# BRD_EPM240.net
KiCad netlist of a schematic drawn in Altium Designer
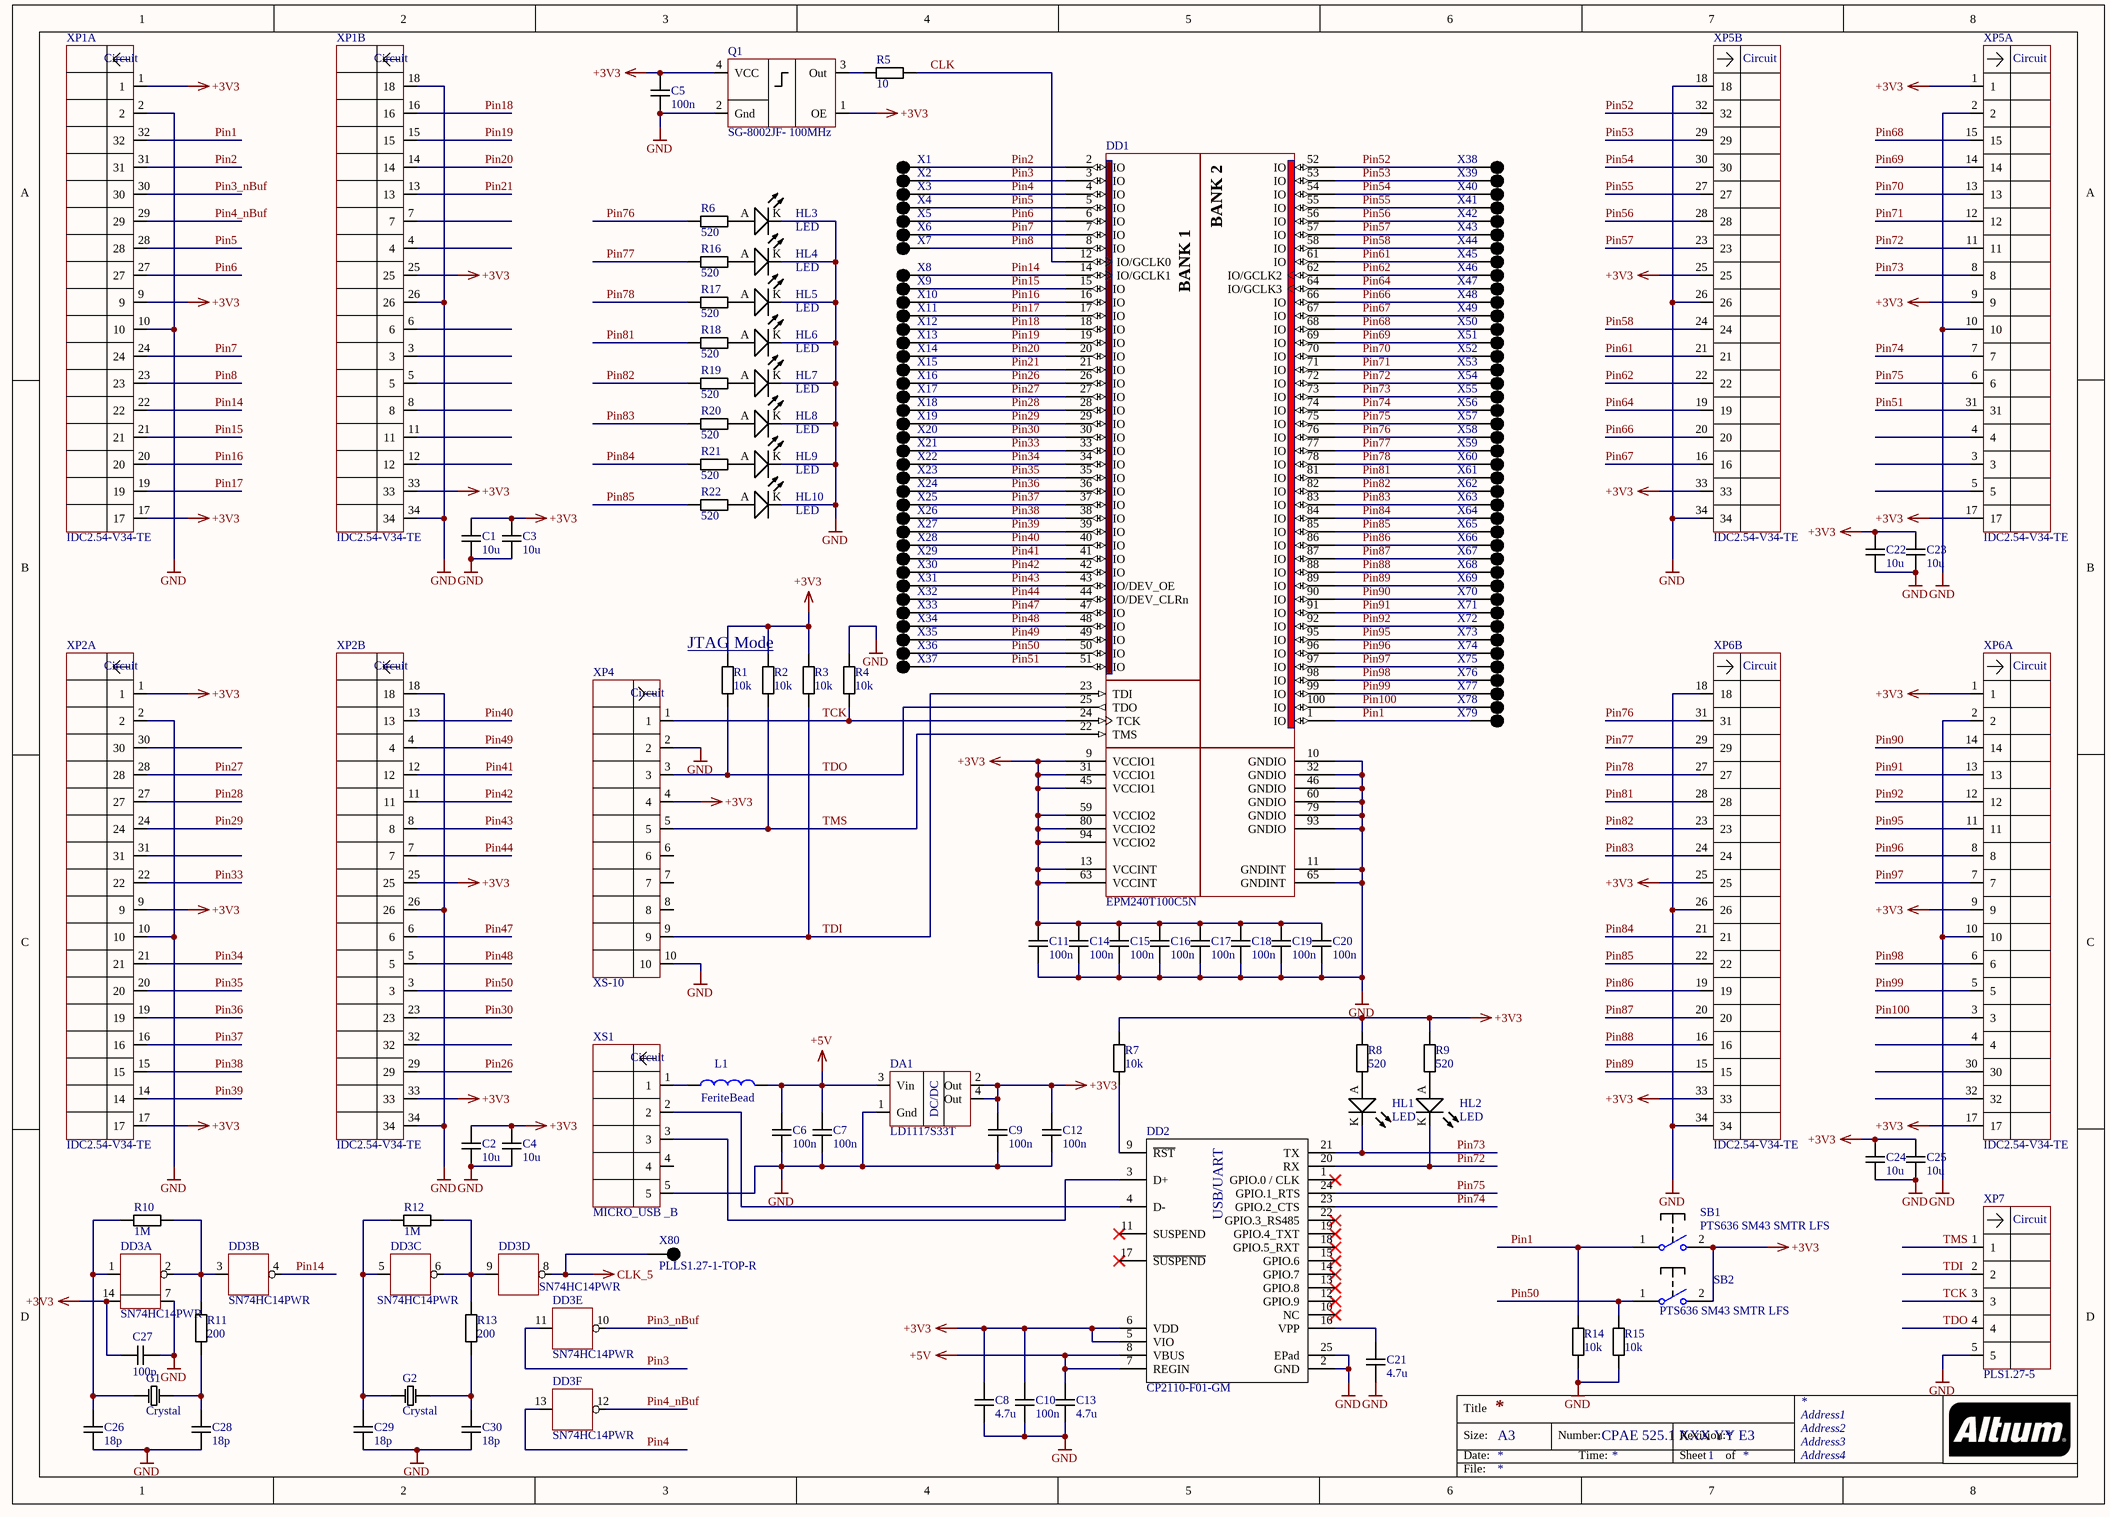
[diagram p0: BRD_EPM240.SchDoc]

(export (version "E")
  (design (tool "Eeschema 10.0.6"))
  (components
    (comp (ref "C1")
      (value "10u")
      (footprint "CAPC1608(0603)N")
      (description "?")
      (fields (field (name "PART NUMBER") "CAPC1608(0603)"))
      (libsource (lib "SssAccesDatbase") (part "Cap"))
    )
    (comp (ref "C2")
      (value "10u")
      (footprint "CAPC1608(0603)N")
      (description "?")
      (fields (field (name "PART NUMBER") "CAPC1608(0603)"))
      (libsource (lib "SssAccesDatbase") (part "Cap"))
    )
    (comp (ref "C3")
      (value "10u")
      (footprint "CAPC1608(0603)N")
      (description "?")
      (fields (field (name "PART NUMBER") "CAPC1608(0603)"))
      (libsource (lib "SssAccesDatbase") (part "Cap"))
    )
    (comp (ref "C4")
      (value "10u")
      (footprint "CAPC1608(0603)N")
      (description "?")
      (fields (field (name "PART NUMBER") "CAPC1608(0603)"))
      (libsource (lib "SssAccesDatbase") (part "Cap"))
    )
    (comp (ref "C5")
      (value "100n")
      (footprint "CAPC1608(0603)N")
      (description "?")
      (fields (field (name "PART NUMBER") "CAPC1608(0603)"))
      (libsource (lib "SssAccesDatbase") (part "Cap"))
    )
    (comp (ref "C6")
      (value "100n")
      (footprint "CAPC1608(0603)N")
      (description "?")
      (fields (field (name "PART NUMBER") "CAPC1608(0603)"))
      (libsource (lib "SssAccesDatbase") (part "Cap"))
    )
    (comp (ref "C7")
      (value "100n")
      (footprint "CAPC1608(0603)N")
      (description "?")
      (fields (field (name "PART NUMBER") "CAPC1608(0603)"))
      (libsource (lib "SssAccesDatbase") (part "Cap"))
    )
    (comp (ref "C8")
      (value "4.7u")
      (footprint "CAPC1608(0603)N")
      (description "?")
      (fields (field (name "PART NUMBER") "CAPC1608(0603)"))
      (libsource (lib "SssAccesDatbase") (part "Cap"))
    )
    (comp (ref "C9")
      (value "100n")
      (footprint "CAPC1608(0603)N")
      (description "?")
      (fields (field (name "PART NUMBER") "CAPC1608(0603)"))
      (libsource (lib "SssAccesDatbase") (part "Cap"))
    )
    (comp (ref "C10")
      (value "100n")
      (footprint "CAPC1608(0603)N")
      (description "?")
      (fields (field (name "PART NUMBER") "CAPC1608(0603)"))
      (libsource (lib "SssAccesDatbase") (part "Cap"))
    )
    (comp (ref "C11")
      (value "100n")
      (footprint "CAPC1608(0603)N")
      (description "?")
      (fields (field (name "PART NUMBER") "CAPC1608(0603)"))
      (libsource (lib "SssAccesDatbase") (part "Cap"))
    )
    (comp (ref "C12")
      (value "100n")
      (footprint "CAPC1608(0603)N")
      (description "?")
      (fields (field (name "PART NUMBER") "CAPC1608(0603)"))
      (libsource (lib "SssAccesDatbase") (part "Cap"))
    )
    (comp (ref "C13")
      (value "4.7u")
      (footprint "CAPC1608(0603)N")
      (description "?")
      (fields (field (name "PART NUMBER") "CAPC1608(0603)"))
      (libsource (lib "SssAccesDatbase") (part "Cap"))
    )
    (comp (ref "C14")
      (value "100n")
      (footprint "CAPC1608(0603)N")
      (description "?")
      (fields (field (name "PART NUMBER") "CAPC1608(0603)"))
      (libsource (lib "SssAccesDatbase") (part "Cap"))
    )
    (comp (ref "C15")
      (value "100n")
      (footprint "CAPC1608(0603)N")
      (description "?")
      (fields (field (name "PART NUMBER") "CAPC1608(0603)"))
      (libsource (lib "SssAccesDatbase") (part "Cap"))
    )
    (comp (ref "C16")
      (value "100n")
      (footprint "CAPC1608(0603)N")
      (description "?")
      (fields (field (name "PART NUMBER") "CAPC1608(0603)"))
      (libsource (lib "SssAccesDatbase") (part "Cap"))
    )
    (comp (ref "C17")
      (value "100n")
      (footprint "CAPC1608(0603)N")
      (description "?")
      (fields (field (name "PART NUMBER") "CAPC1608(0603)"))
      (libsource (lib "SssAccesDatbase") (part "Cap"))
    )
    (comp (ref "C18")
      (value "100n")
      (footprint "CAPC1608(0603)N")
      (description "?")
      (fields (field (name "PART NUMBER") "CAPC1608(0603)"))
      (libsource (lib "SssAccesDatbase") (part "Cap"))
    )
    (comp (ref "C19")
      (value "100n")
      (footprint "CAPC1608(0603)N")
      (description "?")
      (fields (field (name "PART NUMBER") "CAPC1608(0603)"))
      (libsource (lib "SssAccesDatbase") (part "Cap"))
    )
    (comp (ref "C20")
      (value "100n")
      (footprint "CAPC1608(0603)N")
      (description "?")
      (fields (field (name "PART NUMBER") "CAPC1608(0603)"))
      (libsource (lib "SssAccesDatbase") (part "Cap"))
    )
    (comp (ref "C21")
      (value "4.7u")
      (footprint "CAPC1608(0603)N")
      (description "?")
      (fields (field (name "PART NUMBER") "CAPC1608(0603)"))
      (libsource (lib "SssAccesDatbase") (part "Cap"))
    )
    (comp (ref "C22")
      (value "10u")
      (footprint "CAPC1608(0603)N")
      (description "?")
      (fields (field (name "PART NUMBER") "CAPC1608(0603)"))
      (libsource (lib "SssAccesDatbase") (part "Cap"))
    )
    (comp (ref "C23")
      (value "10u")
      (footprint "CAPC1608(0603)N")
      (description "?")
      (fields (field (name "PART NUMBER") "CAPC1608(0603)"))
      (libsource (lib "SssAccesDatbase") (part "Cap"))
    )
    (comp (ref "C24")
      (value "10u")
      (footprint "CAPC1608(0603)N")
      (description "?")
      (fields (field (name "PART NUMBER") "CAPC1608(0603)"))
      (libsource (lib "SssAccesDatbase") (part "Cap"))
    )
    (comp (ref "C25")
      (value "10u")
      (footprint "CAPC1608(0603)N")
      (description "?")
      (fields (field (name "PART NUMBER") "CAPC1608(0603)"))
      (libsource (lib "SssAccesDatbase") (part "Cap"))
    )
    (comp (ref "C26")
      (value "18p")
      (footprint "CAPC1608(0603)N")
      (description "?")
      (fields (field (name "PART NUMBER") "CAPC1608(0603)"))
      (libsource (lib "SssAccesDatbase") (part "Cap"))
    )
    (comp (ref "C27")
      (value "100p")
      (footprint "CAPC1608(0603)N")
      (description "?")
      (fields (field (name "PART NUMBER") "CAPC1608(0603)"))
      (libsource (lib "SssAccesDatbaseDYandex") (part "Cap"))
    )
    (comp (ref "C28")
      (value "18p")
      (footprint "CAPC1608(0603)N")
      (description "?")
      (fields (field (name "PART NUMBER") "CAPC1608(0603)"))
      (libsource (lib "SssAccesDatbase") (part "Cap"))
    )
    (comp (ref "C29")
      (value "18p")
      (footprint "CAPC1608(0603)N")
      (description "?")
      (fields (field (name "PART NUMBER") "CAPC1608(0603)"))
      (libsource (lib "SssAccesDatbase") (part "Cap"))
    )
    (comp (ref "C30")
      (value "18p")
      (footprint "CAPC1608(0603)N")
      (description "?")
      (fields (field (name "PART NUMBER") "CAPC1608(0603)"))
      (libsource (lib "SssAccesDatbase") (part "Cap"))
    )
    (comp (ref "DA1")
      (value "LD1117S33T")
      (footprint "SOT223_M")
      (libsource (lib "ADdatabaseLibfile") (part "LD1117S33T"))
    )
    (comp (ref "DD1")
      (value "EPM240T100C5N")
      (footprint "TQFP100_M")
      (fields (field (name "PUBLISHER") "Altium Limited"))
      (libsource (lib "SssAccesDatbase") (part "EPM240T100C5N"))
    )
    (comp (ref "DD2")
      (value "CP2110-F01-GM")
      (footprint "QFN24_N")
      (description "USB Bridge, USB to UART USB 2.0 UART Interface 24-QFN (4x4)")
      (fields (field (name "DIGI-KEY PART NUMBER") "336-2006-5-ND"))
      (libsource (lib "SssAccesDatbase") (part "CP2110-F01-GM"))
    )
    (comp (ref "DD3")
      (value "SN74HC14PWR")
      (footprint "TSSOP14")
      (description "IC INVERTER SCHMITT 6CH 14TSSOP")
      (libsource (lib "SssAccesDatbase") (part "74HC14"))
    )
    (comp (ref "G1")
      (value "Crystal")
      (footprint "HC-49/S")
      (description "Crystal HC-49/S")
      (libsource (lib "SssAccesDatbaseDYandex") (part "Crystal"))
    )
    (comp (ref "G2")
      (value "Crystal")
      (footprint "HC-49/S")
      (description "Crystal HC-49/S")
      (libsource (lib "SssAccesDatbaseDYandex") (part "Crystal"))
    )
    (comp (ref "HL1")
      (value "LED")
      (footprint "LED-0603-BLUE")
      (description "LED BLUE DIFFUSED 0603 SMD")
      (fields
        (field (name "PART NUMBER") "LED-0603-BLUE")
        (field (name "DIGI-KEY PART NUMBER") "732-12013-1-ND")
      )
      (libsource (lib "SssAccesDatbase") (part "LED"))
    )
    (comp (ref "HL2")
      (value "LED")
      (footprint "LED-0603-GREEN")
      (description "LED GREEN DIFFUSED 0603 SMD")
      (fields
        (field (name "PART NUMBER") "LED-0603-GREEN")
        (field (name "DIGI-KEY PART NUMBER") "732-12017-1-ND")
      )
      (libsource (lib "SssAccesDatbase") (part "LED"))
    )
    (comp (ref "HL3")
      (value "LED")
      (footprint "LED-0603-GREEN")
      (description "LED GREEN DIFFUSED 0603 SMD")
      (fields
        (field (name "PART NUMBER") "LED-0603-GREEN")
        (field (name "DIGI-KEY PART NUMBER") "732-12017-1-ND")
      )
      (libsource (lib "SssAccesDatbase") (part "LED"))
    )
    (comp (ref "HL4")
      (value "LED")
      (footprint "LED-0603-GREEN")
      (description "LED BLUE DIFFUSED 0603 SMD")
      (fields
        (field (name "PART NUMBER") "LED-0603-BLUE")
        (field (name "DIGI-KEY PART NUMBER") "732-12013-1-ND")
      )
      (libsource (lib "SssAccesDatbase") (part "LED"))
    )
    (comp (ref "HL5")
      (value "LED")
      (footprint "LED-0603-GREEN")
      (description "LED BLUE DIFFUSED 0603 SMD")
      (fields
        (field (name "PART NUMBER") "LED-0603-BLUE")
        (field (name "DIGI-KEY PART NUMBER") "732-12013-1-ND")
      )
      (libsource (lib "SssAccesDatbase") (part "LED"))
    )
    (comp (ref "HL6")
      (value "LED")
      (footprint "LED-0603-GREEN")
      (description "LED BLUE DIFFUSED 0603 SMD")
      (fields
        (field (name "PART NUMBER") "LED-0603-BLUE")
        (field (name "DIGI-KEY PART NUMBER") "732-12013-1-ND")
      )
      (libsource (lib "SssAccesDatbase") (part "LED"))
    )
    (comp (ref "HL7")
      (value "LED")
      (footprint "LED-0603-GREEN")
      (description "LED BLUE DIFFUSED 0603 SMD")
      (fields
        (field (name "PART NUMBER") "LED-0603-BLUE")
        (field (name "DIGI-KEY PART NUMBER") "732-12013-1-ND")
      )
      (libsource (lib "SssAccesDatbase") (part "LED"))
    )
    (comp (ref "HL8")
      (value "LED")
      (footprint "LED-0603-GREEN")
      (description "LED BLUE DIFFUSED 0603 SMD")
      (fields
        (field (name "PART NUMBER") "LED-0603-BLUE")
        (field (name "DIGI-KEY PART NUMBER") "732-12013-1-ND")
      )
      (libsource (lib "SssAccesDatbase") (part "LED"))
    )
    (comp (ref "HL9")
      (value "LED")
      (footprint "LED-0603-GREEN")
      (description "LED GREEN DIFFUSED 0603 SMD")
      (fields
        (field (name "PART NUMBER") "LED-0603-GREEN")
        (field (name "DIGI-KEY PART NUMBER") "732-12017-1-ND")
      )
      (libsource (lib "SssAccesDatbase") (part "LED"))
    )
    (comp (ref "HL10")
      (value "LED")
      (footprint "LED-0603-GREEN")
      (description "LED GREEN DIFFUSED 0603 SMD")
      (fields
        (field (name "PART NUMBER") "LED-0603-GREEN")
        (field (name "DIGI-KEY PART NUMBER") "732-12017-1-ND")
      )
      (libsource (lib "SssAccesDatbase") (part "LED"))
    )
    (comp (ref "L1")
      (value "FeriteBead")
      (footprint "INDC1608(0603)N")
      (fields (field (name "PART NUMBER") "INDC1608(0603)"))
      (libsource (lib "ADdatabaseLibfile") (part "L"))
    )
    (comp (ref "Q1")
      (value "SG-8002JF- 100MHz")
      (footprint "SG-8002JF")
      (fields (field (name "PART NUMBER") "SG-8002JF"))
      (libsource (lib "ADdatabaseLibfile") (part "SG-8002JF"))
    )
    (comp (ref "R1")
      (value "10k")
      (footprint "1608[0603]:RESC1608(0603)N")
      (fields (field (name "PART NUMBER") "RESC1005(0402)") (field (name "DIGI-KEY PART NUMBER") "???"))
      (libsource (lib "SssAccesDatbaseDYandex") (part "Resistor general"))
    )
    (comp (ref "R2")
      (value "10k")
      (footprint "1608[0603]:RESC1608(0603)N")
      (fields (field (name "PART NUMBER") "RESC1005(0402)") (field (name "DIGI-KEY PART NUMBER") "???"))
      (libsource (lib "SssAccesDatbaseDYandex") (part "Resistor general"))
    )
    (comp (ref "R3")
      (value "10k")
      (footprint "1608[0603]:RESC1608(0603)N")
      (fields (field (name "PART NUMBER") "RESC1005(0402)") (field (name "DIGI-KEY PART NUMBER") "???"))
      (libsource (lib "SssAccesDatbaseDYandex") (part "Resistor general"))
    )
    (comp (ref "R4")
      (value "10k")
      (footprint "1608[0603]:RESC1608(0603)N")
      (fields (field (name "PART NUMBER") "RESC1005(0402)") (field (name "DIGI-KEY PART NUMBER") "???"))
      (libsource (lib "SssAccesDatbaseDYandex") (part "Resistor general"))
    )
    (comp (ref "R5")
      (value "10")
      (footprint "RESC1608(0603)N")
      (fields (field (name "PART NUMBER") "RESC1608(0603)") (field (name "DIGI-KEY PART NUMBER") "???"))
      (libsource (lib "SssAccesDatbase") (part "Resistor general"))
    )
    (comp (ref "R6")
      (value "520")
      (footprint "RESC1608(0603)N")
      (fields (field (name "PART NUMBER") "RESC1608(0603)") (field (name "DIGI-KEY PART NUMBER") "???"))
      (libsource (lib "") (part "Resistor general_1"))
    )
    (comp (ref "R7")
      (value "10k")
      (footprint "1608[0603]:RESC1608(0603)N")
      (fields (field (name "PART NUMBER") "RESC1005(0402)") (field (name "DIGI-KEY PART NUMBER") "???"))
      (libsource (lib "") (part "Resistor general_2"))
    )
    (comp (ref "R8")
      (value "520")
      (footprint "1608[0603]:RESC1608(0603)N")
      (fields (field (name "PART NUMBER") "RESC1608(0603)") (field (name "DIGI-KEY PART NUMBER") "???"))
      (libsource (lib "SssAccesDatbaseDYandex") (part "Resistor general"))
    )
    (comp (ref "R9")
      (value "520")
      (footprint "1608[0603]:RESC1608(0603)N")
      (fields (field (name "PART NUMBER") "RESC1608(0603)") (field (name "DIGI-KEY PART NUMBER") "???"))
      (libsource (lib "SssAccesDatbaseDYandex") (part "Resistor general"))
    )
    (comp (ref "R10")
      (value "1M")
      (footprint "RESC1608(0603)N")
      (fields (field (name "PART NUMBER") "RESC1608(0603)") (field (name "DIGI-KEY PART NUMBER") "???"))
      (libsource (lib "SssAccesDatbaseDYandex") (part "Resistor general"))
    )
    (comp (ref "R11")
      (value "200")
      (footprint "RESC1608(0603)N")
      (fields (field (name "PART NUMBER") "RESC1608(0603)") (field (name "DIGI-KEY PART NUMBER") "???"))
      (libsource (lib "") (part "Resistor general_3"))
    )
    (comp (ref "R12")
      (value "1M")
      (footprint "RESC1608(0603)N")
      (fields (field (name "PART NUMBER") "RESC1608(0603)") (field (name "DIGI-KEY PART NUMBER") "???"))
      (libsource (lib "SssAccesDatbaseDYandex") (part "Resistor general"))
    )
    (comp (ref "R13")
      (value "200")
      (footprint "RESC1608(0603)N")
      (fields (field (name "PART NUMBER") "RESC1608(0603)") (field (name "DIGI-KEY PART NUMBER") "???"))
      (libsource (lib "") (part "Resistor general_3"))
    )
    (comp (ref "R14")
      (value "10k")
      (footprint "RESC1608(0603)N")
      (fields (field (name "PART NUMBER") "RESC1005(0402)") (field (name "DIGI-KEY PART NUMBER") "???"))
      (libsource (lib "") (part "Resistor general_2"))
    )
    (comp (ref "R15")
      (value "10k")
      (footprint "RESC1608(0603)N")
      (fields (field (name "PART NUMBER") "RESC1005(0402)") (field (name "DIGI-KEY PART NUMBER") "???"))
      (libsource (lib "") (part "Resistor general_2"))
    )
    (comp (ref "R16")
      (value "520")
      (footprint "RESC1608(0603)N")
      (fields (field (name "PART NUMBER") "RESC1608(0603)") (field (name "DIGI-KEY PART NUMBER") "???"))
      (libsource (lib "") (part "Resistor general_1"))
    )
    (comp (ref "R17")
      (value "520")
      (footprint "RESC1608(0603)N")
      (fields (field (name "PART NUMBER") "RESC1608(0603)") (field (name "DIGI-KEY PART NUMBER") "???"))
      (libsource (lib "") (part "Resistor general_1"))
    )
    (comp (ref "R18")
      (value "520")
      (footprint "RESC1608(0603)N")
      (fields (field (name "PART NUMBER") "RESC1608(0603)") (field (name "DIGI-KEY PART NUMBER") "???"))
      (libsource (lib "") (part "Resistor general_1"))
    )
    (comp (ref "R19")
      (value "520")
      (footprint "RESC1608(0603)N")
      (fields (field (name "PART NUMBER") "RESC1608(0603)") (field (name "DIGI-KEY PART NUMBER") "???"))
      (libsource (lib "") (part "Resistor general_1"))
    )
    (comp (ref "R20")
      (value "520")
      (footprint "RESC1608(0603)N")
      (fields (field (name "PART NUMBER") "RESC1608(0603)") (field (name "DIGI-KEY PART NUMBER") "???"))
      (libsource (lib "") (part "Resistor general_1"))
    )
    (comp (ref "R21")
      (value "520")
      (footprint "RESC1608(0603)N")
      (fields (field (name "PART NUMBER") "RESC1608(0603)") (field (name "DIGI-KEY PART NUMBER") "???"))
      (libsource (lib "") (part "Resistor general_1"))
    )
    (comp (ref "R22")
      (value "520")
      (footprint "RESC1608(0603)N")
      (fields (field (name "PART NUMBER") "RESC1608(0603)") (field (name "DIGI-KEY PART NUMBER") "???"))
      (libsource (lib "") (part "Resistor general_1"))
    )
    (comp (ref "SB1")
      (value "PTS636 SM43 SMTR LFS")
      (footprint "PTS636 SM43 SMTR LFS")
      (description "Tactile Switches Tact 50mA 12VDC, 6.0x3.5, 4.3mm H, 180gf, G leads, No ground pin, Black Actuator")
      (fields (field (name "MOUSER PART NUMBER") "611-PTS636SM43SMTRLF"))
      (libsource (lib "SssAccesDatbase") (part "SW-SPST"))
    )
    (comp (ref "SB2")
      (value "PTS636 SM43 SMTR LFS")
      (footprint "PTS636 SM43 SMTR LFS")
      (description "Tactile Switches Tact 50mA 12VDC, 6.0x3.5, 4.3mm H, 180gf, G leads, No ground pin, Black Actuator")
      (fields (field (name "MOUSER PART NUMBER") "611-PTS636SM43SMTRLF"))
      (libsource (lib "SssAccesDatbase") (part "SW-SPST"))
    )
    (comp (ref "X1")
      (value "X1-PLLD1.27-1")
      (footprint "PLLS1.27-1")
      (libsource (lib "SssAccesDatbase") (part "X1_1"))
    )
    (comp (ref "X2")
      (value "X1-PLLD1.27-1")
      (footprint "PLLS1.27-1")
      (libsource (lib "SssAccesDatbase") (part "X1_1"))
    )
    (comp (ref "X3")
      (value "X1-PLLD1.27-1")
      (footprint "PLLS1.27-1")
      (libsource (lib "SssAccesDatbase") (part "X1_1"))
    )
    (comp (ref "X4")
      (value "X1-PLLD1.27-1")
      (footprint "PLLS1.27-1")
      (libsource (lib "SssAccesDatbase") (part "X1_1"))
    )
    (comp (ref "X5")
      (value "X1-PLLD1.27-1")
      (footprint "PLLS1.27-1")
      (libsource (lib "SssAccesDatbase") (part "X1_1"))
    )
    (comp (ref "X6")
      (value "X1-PLLD1.27-1")
      (footprint "PLLS1.27-1")
      (libsource (lib "SssAccesDatbase") (part "X1_1"))
    )
    (comp (ref "X7")
      (value "X1-PLLD1.27-1")
      (footprint "PLLS1.27-1")
      (libsource (lib "SssAccesDatbase") (part "X1_1"))
    )
    (comp (ref "X8")
      (value "X1-PLLD1.27-1")
      (footprint "PLLS1.27-1")
      (libsource (lib "SssAccesDatbase") (part "X1_1"))
    )
    (comp (ref "X9")
      (value "X1-PLLD1.27-1")
      (footprint "PLLS1.27-1")
      (libsource (lib "SssAccesDatbase") (part "X1_1"))
    )
    (comp (ref "X10")
      (value "X1-PLLD1.27-1")
      (footprint "PLLS1.27-1")
      (libsource (lib "SssAccesDatbase") (part "X1_1"))
    )
    (comp (ref "X11")
      (value "X1-PLLD1.27-1")
      (footprint "PLLS1.27-1")
      (libsource (lib "SssAccesDatbase") (part "X1_1"))
    )
    (comp (ref "X12")
      (value "X1-PLLD1.27-1")
      (footprint "PLLS1.27-1")
      (libsource (lib "SssAccesDatbase") (part "X1_1"))
    )
    (comp (ref "X13")
      (value "X1-PLLD1.27-1")
      (footprint "PLLS1.27-1")
      (libsource (lib "SssAccesDatbase") (part "X1_1"))
    )
    (comp (ref "X14")
      (value "X1-PLLD1.27-1")
      (footprint "PLLS1.27-1")
      (libsource (lib "SssAccesDatbase") (part "X1_1"))
    )
    (comp (ref "X15")
      (value "X1-PLLD1.27-1")
      (footprint "PLLS1.27-1")
      (libsource (lib "SssAccesDatbase") (part "X1_1"))
    )
    (comp (ref "X16")
      (value "X1-PLLD1.27-1")
      (footprint "PLLS1.27-1")
      (libsource (lib "SssAccesDatbase") (part "X1_1"))
    )
    (comp (ref "X17")
      (value "X1-PLLD1.27-1")
      (footprint "PLLS1.27-1")
      (libsource (lib "SssAccesDatbase") (part "X1_1"))
    )
    (comp (ref "X18")
      (value "X1-PLLD1.27-1")
      (footprint "PLLS1.27-1")
      (libsource (lib "SssAccesDatbase") (part "X1_1"))
    )
    (comp (ref "X19")
      (value "X1-PLLD1.27-1")
      (footprint "PLLS1.27-1")
      (libsource (lib "SssAccesDatbase") (part "X1_1"))
    )
    (comp (ref "X20")
      (value "X1-PLLD1.27-1")
      (footprint "PLLS1.27-1")
      (libsource (lib "SssAccesDatbase") (part "X1_1"))
    )
    (comp (ref "X21")
      (value "X1-PLLD1.27-1")
      (footprint "PLLS1.27-1")
      (libsource (lib "SssAccesDatbase") (part "X1_1"))
    )
    (comp (ref "X22")
      (value "X1-PLLD1.27-1")
      (footprint "PLLS1.27-1")
      (libsource (lib "SssAccesDatbase") (part "X1_1"))
    )
    (comp (ref "X23")
      (value "X1-PLLD1.27-1")
      (footprint "PLLS1.27-1")
      (libsource (lib "SssAccesDatbase") (part "X1_1"))
    )
    (comp (ref "X24")
      (value "X1-PLLD1.27-1")
      (footprint "PLLS1.27-1")
      (libsource (lib "SssAccesDatbase") (part "X1_1"))
    )
    (comp (ref "X25")
      (value "X1-PLLD1.27-1")
      (footprint "PLLS1.27-1")
      (libsource (lib "SssAccesDatbase") (part "X1_1"))
    )
    (comp (ref "X26")
      (value "X1-PLLD1.27-1")
      (footprint "PLLS1.27-1")
      (libsource (lib "SssAccesDatbase") (part "X1_1"))
    )
    (comp (ref "X27")
      (value "X1-PLLD1.27-1")
      (footprint "PLLS1.27-1")
      (libsource (lib "SssAccesDatbase") (part "X1_1"))
    )
    (comp (ref "X28")
      (value "X1-PLLD1.27-1")
      (footprint "PLLS1.27-1")
      (libsource (lib "SssAccesDatbase") (part "X1_1"))
    )
    (comp (ref "X29")
      (value "X1-PLLD1.27-1")
      (footprint "PLLS1.27-1")
      (libsource (lib "SssAccesDatbase") (part "X1_1"))
    )
    (comp (ref "X30")
      (value "X1-PLLD1.27-1")
      (footprint "PLLS1.27-1")
      (libsource (lib "SssAccesDatbase") (part "X1_1"))
    )
    (comp (ref "X31")
      (value "X1-PLLD1.27-1")
      (footprint "PLLS1.27-1")
      (libsource (lib "SssAccesDatbase") (part "X1_1"))
    )
    (comp (ref "X32")
      (value "X1-PLLD1.27-1")
      (footprint "PLLS1.27-1")
      (libsource (lib "SssAccesDatbase") (part "X1_1"))
    )
    (comp (ref "X33")
      (value "X1-PLLD1.27-1")
      (footprint "PLLS1.27-1")
      (libsource (lib "SssAccesDatbase") (part "X1_1"))
    )
    (comp (ref "X34")
      (value "X1-PLLD1.27-1")
      (footprint "PLLS1.27-1")
      (libsource (lib "SssAccesDatbase") (part "X1_1"))
    )
    (comp (ref "X35")
      (value "X1-PLLD1.27-1")
      (footprint "PLLS1.27-1")
      (libsource (lib "SssAccesDatbase") (part "X1_1"))
    )
    (comp (ref "X36")
      (value "X1-PLLD1.27-1")
      (footprint "PLLS1.27-1")
      (libsource (lib "SssAccesDatbase") (part "X1_1"))
    )
    (comp (ref "X37")
      (value "X1-PLLD1.27-1")
      (footprint "PLLS1.27-1")
      (libsource (lib "SssAccesDatbase") (part "X1_1"))
    )
    (comp (ref "X38")
      (value "X1-PLLD1.27-1")
      (footprint "PLLS1.27-1")
      (libsource (lib "SssAccesDatbase") (part "X1_1"))
    )
    (comp (ref "X39")
      (value "X1-PLLD1.27-1")
      (footprint "PLLS1.27-1")
      (libsource (lib "SssAccesDatbase") (part "X1_1"))
    )
    (comp (ref "X40")
      (value "X1-PLLD1.27-1")
      (footprint "PLLS1.27-1")
      (libsource (lib "SssAccesDatbase") (part "X1_1"))
    )
    (comp (ref "X41")
      (value "X1-PLLD1.27-1")
      (footprint "PLLS1.27-1")
      (libsource (lib "SssAccesDatbase") (part "X1_1"))
    )
    (comp (ref "X42")
      (value "X1-PLLD1.27-1")
      (footprint "PLLS1.27-1")
      (libsource (lib "SssAccesDatbase") (part "X1_1"))
    )
    (comp (ref "X43")
      (value "X1-PLLD1.27-1")
      (footprint "PLLS1.27-1")
      (libsource (lib "SssAccesDatbase") (part "X1_1"))
    )
    (comp (ref "X44")
      (value "X1-PLLD1.27-1")
      (footprint "PLLS1.27-1")
      (libsource (lib "SssAccesDatbase") (part "X1_1"))
    )
    (comp (ref "X45")
      (value "X1-PLLD1.27-1")
      (footprint "PLLS1.27-1")
      (libsource (lib "SssAccesDatbase") (part "X1_1"))
    )
    (comp (ref "X46")
      (value "X1-PLLD1.27-1")
      (footprint "PLLS1.27-1")
      (libsource (lib "SssAccesDatbase") (part "X1_1"))
    )
    (comp (ref "X47")
      (value "X1-PLLD1.27-1")
      (footprint "PLLS1.27-1")
      (libsource (lib "SssAccesDatbase") (part "X1_1"))
    )
    (comp (ref "X48")
      (value "X1-PLLD1.27-1")
      (footprint "PLLS1.27-1")
      (libsource (lib "SssAccesDatbase") (part "X1_1"))
    )
    (comp (ref "X49")
      (value "X1-PLLD1.27-1")
      (footprint "PLLS1.27-1")
      (libsource (lib "SssAccesDatbase") (part "X1_1"))
    )
    (comp (ref "X50")
      (value "X1-PLLD1.27-1")
      (footprint "PLLS1.27-1")
      (libsource (lib "SssAccesDatbase") (part "X1_1"))
    )
    (comp (ref "X51")
      (value "X1-PLLD1.27-1")
      (footprint "PLLS1.27-1")
      (libsource (lib "SssAccesDatbase") (part "X1_1"))
    )
    (comp (ref "X52")
      (value "X1-PLLD1.27-1")
      (footprint "PLLS1.27-1")
      (libsource (lib "SssAccesDatbase") (part "X1_1"))
    )
    (comp (ref "X53")
      (value "X1-PLLD1.27-1")
      (footprint "PLLS1.27-1")
      (libsource (lib "SssAccesDatbase") (part "X1_1"))
    )
    (comp (ref "X54")
      (value "X1-PLLD1.27-1")
      (footprint "PLLS1.27-1")
      (libsource (lib "SssAccesDatbase") (part "X1_1"))
    )
    (comp (ref "X55")
      (value "X1-PLLD1.27-1")
      (footprint "PLLS1.27-1")
      (libsource (lib "SssAccesDatbase") (part "X1_1"))
    )
    (comp (ref "X56")
      (value "X1-PLLD1.27-1")
      (footprint "PLLS1.27-1")
      (libsource (lib "SssAccesDatbase") (part "X1_1"))
    )
    (comp (ref "X57")
      (value "X1-PLLD1.27-1")
      (footprint "PLLS1.27-1")
      (libsource (lib "SssAccesDatbase") (part "X1_1"))
    )
    (comp (ref "X58")
      (value "X1-PLLD1.27-1")
      (footprint "PLLS1.27-1")
      (libsource (lib "SssAccesDatbase") (part "X1_1"))
    )
    (comp (ref "X59")
      (value "X1-PLLD1.27-1")
      (footprint "PLLS1.27-1")
      (libsource (lib "SssAccesDatbase") (part "X1_1"))
    )
    (comp (ref "X60")
      (value "X1-PLLD1.27-1")
      (footprint "PLLS1.27-1")
      (libsource (lib "SssAccesDatbase") (part "X1_1"))
    )
    (comp (ref "X61")
      (value "X1-PLLD1.27-1")
      (footprint "PLLS1.27-1")
      (libsource (lib "SssAccesDatbase") (part "X1_1"))
    )
    (comp (ref "X62")
      (value "X1-PLLD1.27-1")
      (footprint "PLLS1.27-1")
      (libsource (lib "SssAccesDatbase") (part "X1_1"))
    )
    (comp (ref "X63")
      (value "X1-PLLD1.27-1")
      (footprint "PLLS1.27-1")
      (libsource (lib "SssAccesDatbase") (part "X1_1"))
    )
    (comp (ref "X64")
      (value "X1-PLLD1.27-1")
      (footprint "PLLS1.27-1")
      (libsource (lib "SssAccesDatbase") (part "X1_1"))
    )
    (comp (ref "X65")
      (value "X1-PLLD1.27-1")
      (footprint "PLLS1.27-1")
      (libsource (lib "SssAccesDatbase") (part "X1_1"))
    )
    (comp (ref "X66")
      (value "X1-PLLD1.27-1")
      (footprint "PLLS1.27-1")
      (libsource (lib "SssAccesDatbase") (part "X1_1"))
    )
    (comp (ref "X67")
      (value "X1-PLLD1.27-1")
      (footprint "PLLS1.27-1")
      (libsource (lib "SssAccesDatbase") (part "X1_1"))
    )
    (comp (ref "X68")
      (value "X1-PLLD1.27-1")
      (footprint "PLLS1.27-1")
      (libsource (lib "SssAccesDatbase") (part "X1_1"))
    )
    (comp (ref "X69")
      (value "X1-PLLD1.27-1")
      (footprint "PLLS1.27-1")
      (libsource (lib "SssAccesDatbase") (part "X1_1"))
    )
    (comp (ref "X70")
      (value "X1-PLLD1.27-1")
      (footprint "PLLS1.27-1")
      (libsource (lib "SssAccesDatbase") (part "X1_1"))
    )
    (comp (ref "X71")
      (value "X1-PLLD1.27-1")
      (footprint "PLLS1.27-1")
      (libsource (lib "SssAccesDatbase") (part "X1_1"))
    )
    (comp (ref "X72")
      (value "X1-PLLD1.27-1")
      (footprint "PLLS1.27-1")
      (libsource (lib "SssAccesDatbase") (part "X1_1"))
    )
    (comp (ref "X73")
      (value "X1-PLLD1.27-1")
      (footprint "PLLS1.27-1")
      (libsource (lib "SssAccesDatbase") (part "X1_1"))
    )
    (comp (ref "X74")
      (value "X1-PLLD1.27-1")
      (footprint "PLLS1.27-1")
      (libsource (lib "SssAccesDatbase") (part "X1_1"))
    )
    (comp (ref "X75")
      (value "X1-PLLD1.27-1")
      (footprint "PLLS1.27-1")
      (libsource (lib "SssAccesDatbase") (part "X1_1"))
    )
    (comp (ref "X76")
      (value "X1-PLLD1.27-1")
      (footprint "PLLS1.27-1")
      (libsource (lib "SssAccesDatbase") (part "X1_1"))
    )
    (comp (ref "X77")
      (value "X1-PLLD1.27-1")
      (footprint "PLLS1.27-1")
      (libsource (lib "SssAccesDatbase") (part "X1_1"))
    )
    (comp (ref "X78")
      (value "X1-PLLD1.27-1")
      (footprint "PLLS1.27-1")
      (libsource (lib "SssAccesDatbase") (part "X1_1"))
    )
    (comp (ref "X79")
      (value "X1-PLLD1.27-1")
      (footprint "PLLS1.27-1")
      (libsource (lib "SssAccesDatbase") (part "X1_1"))
    )
    (comp (ref "X80")
      (value "PLLS1.27-1-TOP-R")
      (footprint "PLLS1.27-1-TOP-R")
      (libsource (lib "SssAccesDatbase") (part "X1_1"))
    )
    (comp (ref "XP1")
      (value "IDC2.54-V34-TE")
      (footprint "IDC2.54-V34-TE")
      (libsource (lib "") (part "XP-34_3"))
    )
    (comp (ref "XP2")
      (value "IDC2.54-V34-TE")
      (footprint "IDC2.54-V34-TE")
      (libsource (lib "") (part "XP-34_7"))
    )
    (comp (ref "XP4")
      (value "XS-10")
      (footprint "BH-10")
      (fields
        (field (name "PART NUMBER") "3220-10-0100-00")
        (field (name "DIGI-KEY PART NUMBER") "1175-1627-ND")
      )
      (libsource (lib "ADdatabaseLibfile") (part "XS-10"))
    )
    (comp (ref "XP5")
      (value "IDC2.54-V34-TE")
      (footprint "IDC2.54-V34-TE")
      (libsource (lib "") (part "XP-34_1"))
    )
    (comp (ref "XP6")
      (value "IDC2.54-V34-TE")
      (footprint "IDC2.54-V34-TE")
      (libsource (lib "") (part "XP-34_2"))
    )
    (comp (ref "XP7")
      (value "PLS1.27-5")
      (footprint "PLLS1.27-5")
      (description "CONN HEADER VERT 5POS 1.27MM")
      (fields
        (field (name "DIGI-KEY PART NUMBER") "952-3601-ND")
        (field (name "MANUFACTURER PART NUMBER") "M50-3530542")
      )
      (libsource (lib "SssAccesDatbase") (part "XP-5"))
    )
    (comp (ref "XS1")
      (value "MICRO_USB _B")
      (footprint "MICRO_USB _B")
      (fields (field (name "DIGI-KEY PART NUMBER") "???"))
      (libsource (lib "SssAccesDatbase") (part "Micro USB"))
    )
  )
  (nets
    (net (code "1") (name "+3V3") (class "Default")
      (node (ref "C1") (pin "2") (pinfunction "2_2") (pintype "passive"))
      (node (ref "C10") (pin "2") (pinfunction "2_2") (pintype "passive"))
      (node (ref "C11") (pin "2") (pinfunction "2_2") (pintype "passive"))
      (node (ref "C12") (pin "2") (pinfunction "2_2") (pintype "passive"))
      (node (ref "C14") (pin "2") (pinfunction "2_2") (pintype "passive"))
      (node (ref "C15") (pin "2") (pinfunction "2_2") (pintype "passive"))
      (node (ref "C16") (pin "2") (pinfunction "2_2") (pintype "passive"))
      (node (ref "C17") (pin "2") (pinfunction "2_2") (pintype "passive"))
      (node (ref "C18") (pin "2") (pinfunction "2_2") (pintype "passive"))
      (node (ref "C19") (pin "2") (pinfunction "2_2") (pintype "passive"))
      (node (ref "C2") (pin "2") (pinfunction "2_2") (pintype "passive"))
      (node (ref "C20") (pin "2") (pinfunction "2_2") (pintype "passive"))
      (node (ref "C22") (pin "2") (pinfunction "2_2") (pintype "passive"))
      (node (ref "C23") (pin "2") (pinfunction "2_2") (pintype "passive"))
      (node (ref "C24") (pin "2") (pinfunction "2_2") (pintype "passive"))
      (node (ref "C25") (pin "2") (pinfunction "2_2") (pintype "passive"))
      (node (ref "C27") (pin "1") (pinfunction "1_1") (pintype "passive"))
      (node (ref "C3") (pin "2") (pinfunction "2_2") (pintype "passive"))
      (node (ref "C4") (pin "2") (pinfunction "2_2") (pintype "passive"))
      (node (ref "C5") (pin "2") (pinfunction "2_2") (pintype "passive"))
      (node (ref "C8") (pin "2") (pinfunction "2_2") (pintype "passive"))
      (node (ref "C9") (pin "2") (pinfunction "2_2") (pintype "passive"))
      (node (ref "DA1") (pin "2") (pinfunction "Out_2") (pintype "passive"))
      (node (ref "DA1") (pin "4") (pinfunction "Out_4") (pintype "passive"))
      (node (ref "DD1") (pin "13") (pinfunction "VCCINT_13") (pintype "power_in"))
      (node (ref "DD1") (pin "31") (pinfunction "VCCIO1_31") (pintype "power_in"))
      (node (ref "DD1") (pin "45") (pinfunction "VCCIO1_45") (pintype "power_in"))
      (node (ref "DD1") (pin "59") (pinfunction "VCCIO2_59") (pintype "power_in"))
      (node (ref "DD1") (pin "63") (pinfunction "VCCINT_63") (pintype "power_in"))
      (node (ref "DD1") (pin "80") (pinfunction "VCCIO2_80") (pintype "power_in"))
      (node (ref "DD1") (pin "9") (pinfunction "VCCIO1_9") (pintype "power_in"))
      (node (ref "DD1") (pin "94") (pinfunction "VCCIO2_94") (pintype "power_in"))
      (node (ref "DD2") (pin "5") (pinfunction "VIO_5") (pintype "passive"))
      (node (ref "DD2") (pin "6") (pinfunction "VDD_6") (pintype "passive"))
      (node (ref "DD3") (pin "14") (pinfunction "VCC_14") (pintype "power_in"))
      (node (ref "Q1") (pin "1") (pinfunction "OE_1") (pintype "passive"))
      (node (ref "Q1") (pin "4") (pinfunction "VCC_4") (pintype "passive"))
      (node (ref "R1") (pin "2") (pinfunction "2_2") (pintype "passive"))
      (node (ref "R2") (pin "2") (pinfunction "2_2") (pintype "passive"))
      (node (ref "R3") (pin "2") (pinfunction "2_2") (pintype "passive"))
      (node (ref "R7") (pin "1") (pinfunction "1_1") (pintype "passive"))
      (node (ref "R8") (pin "2") (pinfunction "2_2") (pintype "passive"))
      (node (ref "R9") (pin "2") (pinfunction "2_2") (pintype "passive"))
      (node (ref "SB1") (pin "2") (pinfunction "NO_2") (pintype "passive"))
      (node (ref "SB2") (pin "2") (pinfunction "NO_2") (pintype "passive"))
      (node (ref "XP1") (pin "1") (pinfunction "1_1") (pintype "passive"))
      (node (ref "XP1") (pin "17") (pinfunction "17_17") (pintype "passive"))
      (node (ref "XP1") (pin "25") (pinfunction "25_25") (pintype "passive"))
      (node (ref "XP1") (pin "33") (pinfunction "33_33") (pintype "passive"))
      (node (ref "XP1") (pin "9") (pinfunction "9_9") (pintype "passive"))
      (node (ref "XP2") (pin "1") (pinfunction "1_1") (pintype "passive"))
      (node (ref "XP2") (pin "17") (pinfunction "17_17") (pintype "passive"))
      (node (ref "XP2") (pin "25") (pinfunction "25_25") (pintype "passive"))
      (node (ref "XP2") (pin "33") (pinfunction "33_33") (pintype "passive"))
      (node (ref "XP2") (pin "9") (pinfunction "9_9") (pintype "passive"))
      (node (ref "XP4") (pin "4") (pinfunction "4_4") (pintype "passive"))
      (node (ref "XP5") (pin "1") (pinfunction "1_1") (pintype "passive"))
      (node (ref "XP5") (pin "17") (pinfunction "17_17") (pintype "passive"))
      (node (ref "XP5") (pin "25") (pinfunction "25_25") (pintype "passive"))
      (node (ref "XP5") (pin "33") (pinfunction "33_33") (pintype "passive"))
      (node (ref "XP5") (pin "9") (pinfunction "9_9") (pintype "passive"))
      (node (ref "XP6") (pin "1") (pinfunction "1_1") (pintype "passive"))
      (node (ref "XP6") (pin "17") (pinfunction "17_17") (pintype "passive"))
      (node (ref "XP6") (pin "25") (pinfunction "25_25") (pintype "passive"))
      (node (ref "XP6") (pin "33") (pinfunction "33_33") (pintype "passive"))
      (node (ref "XP6") (pin "9") (pinfunction "9_9") (pintype "passive"))
    )
    (net (code "2") (name "+5V") (class "Default")
      (node (ref "C13") (pin "2") (pinfunction "2_2") (pintype "passive"))
      (node (ref "C6") (pin "2") (pinfunction "2_2") (pintype "passive"))
      (node (ref "C7") (pin "2") (pinfunction "2_2") (pintype "passive"))
      (node (ref "DA1") (pin "3") (pinfunction "Vin_3") (pintype "passive"))
      (node (ref "DD2") (pin "7") (pinfunction "REGIN_7") (pintype "passive"))
      (node (ref "DD2") (pin "8") (pinfunction "VBUS_8") (pintype "passive"))
      (node (ref "L1") (pin "2") (pinfunction "2_2") (pintype "passive"))
    )
    (net (code "3") (name "/CLK") (class "Default")
      (node (ref "DD1") (pin "12") (pinfunction "IO/GCLK0_12") (pintype "bidirectional"))
      (node (ref "R5") (pin "2") (pinfunction "2_2") (pintype "passive"))
    )
    (net (code "4") (name "/Pin1") (class "Default")
      (node (ref "DD1") (pin "1") (pinfunction "IO_1") (pintype "bidirectional"))
      (node (ref "R14") (pin "1") (pinfunction "1_1") (pintype "passive"))
      (node (ref "SB1") (pin "1") (pinfunction "COMMON_1") (pintype "passive"))
      (node (ref "X79") (pin "1") (pinfunction "1_1") (pintype "passive"))
      (node (ref "XP1") (pin "32") (pinfunction "32_32") (pintype "passive"))
    )
    (net (code "5") (name "/Pin2") (class "Default")
      (node (ref "DD1") (pin "2") (pinfunction "IO_2") (pintype "bidirectional"))
      (node (ref "X1") (pin "1") (pinfunction "1_1") (pintype "passive"))
      (node (ref "XP1") (pin "31") (pinfunction "31_31") (pintype "passive"))
    )
    (net (code "6") (name "/Pin3") (class "Default")
      (node (ref "DD1") (pin "3") (pinfunction "IO_3") (pintype "bidirectional"))
      (node (ref "DD3") (pin "11") (pinfunction "5A_11") (pintype "passive"))
      (node (ref "X2") (pin "1") (pinfunction "1_1") (pintype "passive"))
    )
    (net (code "7") (name "/Pin3_nBuf") (class "Default")
      (node (ref "DD3") (pin "10") (pinfunction "5Y_10") (pintype "passive"))
      (node (ref "XP1") (pin "30") (pinfunction "30_30") (pintype "passive"))
    )
    (net (code "8") (name "/Pin4") (class "Default")
      (node (ref "DD1") (pin "4") (pinfunction "IO_4") (pintype "bidirectional"))
      (node (ref "DD3") (pin "13") (pinfunction "6A_13") (pintype "passive"))
      (node (ref "X3") (pin "1") (pinfunction "1_1") (pintype "passive"))
    )
    (net (code "9") (name "/Pin4_nBuf") (class "Default")
      (node (ref "DD3") (pin "12") (pinfunction "6Y_12") (pintype "passive"))
      (node (ref "XP1") (pin "29") (pinfunction "29_29") (pintype "passive"))
    )
    (net (code "10") (name "/Pin5") (class "Default")
      (node (ref "DD1") (pin "5") (pinfunction "IO_5") (pintype "bidirectional"))
      (node (ref "X4") (pin "1") (pinfunction "1_1") (pintype "passive"))
      (node (ref "XP1") (pin "28") (pinfunction "28_28") (pintype "passive"))
    )
    (net (code "11") (name "/Pin6") (class "Default")
      (node (ref "DD1") (pin "6") (pinfunction "IO_6") (pintype "bidirectional"))
      (node (ref "X5") (pin "1") (pinfunction "1_1") (pintype "passive"))
      (node (ref "XP1") (pin "27") (pinfunction "27_27") (pintype "passive"))
    )
    (net (code "12") (name "/Pin7") (class "Default")
      (node (ref "DD1") (pin "7") (pinfunction "IO_7") (pintype "bidirectional"))
      (node (ref "X6") (pin "1") (pinfunction "1_1") (pintype "passive"))
      (node (ref "XP1") (pin "24") (pinfunction "24_24") (pintype "passive"))
    )
    (net (code "13") (name "/Pin8") (class "Default")
      (node (ref "DD1") (pin "8") (pinfunction "IO_8") (pintype "bidirectional"))
      (node (ref "X7") (pin "1") (pinfunction "1_1") (pintype "passive"))
      (node (ref "XP1") (pin "23") (pinfunction "23_23") (pintype "passive"))
    )
    (net (code "14") (name "/Pin14") (class "Default")
      (node (ref "DD1") (pin "14") (pinfunction "IO/GCLK1_14") (pintype "bidirectional"))
      (node (ref "DD3") (pin "4") (pinfunction "2Y_4") (pintype "passive"))
      (node (ref "X8") (pin "1") (pinfunction "1_1") (pintype "passive"))
      (node (ref "XP1") (pin "22") (pinfunction "22_22") (pintype "passive"))
    )
    (net (code "15") (name "/Pin15") (class "Default")
      (node (ref "DD1") (pin "15") (pinfunction "IO_15") (pintype "bidirectional"))
      (node (ref "X9") (pin "1") (pinfunction "1_1") (pintype "passive"))
      (node (ref "XP1") (pin "21") (pinfunction "21_21") (pintype "passive"))
    )
    (net (code "16") (name "/Pin16") (class "Default")
      (node (ref "DD1") (pin "16") (pinfunction "IO_16") (pintype "bidirectional"))
      (node (ref "X10") (pin "1") (pinfunction "1_1") (pintype "passive"))
      (node (ref "XP1") (pin "20") (pinfunction "20_20") (pintype "passive"))
    )
    (net (code "17") (name "/Pin17") (class "Default")
      (node (ref "DD1") (pin "17") (pinfunction "IO_17") (pintype "bidirectional"))
      (node (ref "X11") (pin "1") (pinfunction "1_1") (pintype "passive"))
      (node (ref "XP1") (pin "19") (pinfunction "19_19") (pintype "passive"))
    )
    (net (code "18") (name "/Pin18") (class "Default")
      (node (ref "DD1") (pin "18") (pinfunction "IO_18") (pintype "bidirectional"))
      (node (ref "X12") (pin "1") (pinfunction "1_1") (pintype "passive"))
      (node (ref "XP1") (pin "16") (pinfunction "16_16") (pintype "passive"))
    )
    (net (code "19") (name "/Pin19") (class "Default")
      (node (ref "DD1") (pin "19") (pinfunction "IO_19") (pintype "bidirectional"))
      (node (ref "X13") (pin "1") (pinfunction "1_1") (pintype "passive"))
      (node (ref "XP1") (pin "15") (pinfunction "15_15") (pintype "passive"))
    )
    (net (code "20") (name "/Pin20") (class "Default")
      (node (ref "DD1") (pin "20") (pinfunction "IO_20") (pintype "bidirectional"))
      (node (ref "X14") (pin "1") (pinfunction "1_1") (pintype "passive"))
      (node (ref "XP1") (pin "14") (pinfunction "14_14") (pintype "passive"))
    )
    (net (code "21") (name "/Pin21") (class "Default")
      (node (ref "DD1") (pin "21") (pinfunction "IO_21") (pintype "bidirectional"))
      (node (ref "X15") (pin "1") (pinfunction "1_1") (pintype "passive"))
      (node (ref "XP1") (pin "13") (pinfunction "13_13") (pintype "passive"))
    )
    (net (code "22") (name "/Pin26") (class "Default")
      (node (ref "DD1") (pin "26") (pinfunction "IO_26") (pintype "bidirectional"))
      (node (ref "X16") (pin "1") (pinfunction "1_1") (pintype "passive"))
      (node (ref "XP2") (pin "29") (pinfunction "29_29") (pintype "passive"))
    )
    (net (code "23") (name "/Pin27") (class "Default")
      (node (ref "DD1") (pin "27") (pinfunction "IO_27") (pintype "bidirectional"))
      (node (ref "X17") (pin "1") (pinfunction "1_1") (pintype "passive"))
      (node (ref "XP2") (pin "28") (pinfunction "28_28") (pintype "passive"))
    )
    (net (code "24") (name "/Pin28") (class "Default")
      (node (ref "DD1") (pin "28") (pinfunction "IO_28") (pintype "bidirectional"))
      (node (ref "X18") (pin "1") (pinfunction "1_1") (pintype "passive"))
      (node (ref "XP2") (pin "27") (pinfunction "27_27") (pintype "passive"))
    )
    (net (code "25") (name "/Pin29") (class "Default")
      (node (ref "DD1") (pin "29") (pinfunction "IO_29") (pintype "bidirectional"))
      (node (ref "X19") (pin "1") (pinfunction "1_1") (pintype "passive"))
      (node (ref "XP2") (pin "24") (pinfunction "24_24") (pintype "passive"))
    )
    (net (code "26") (name "/Pin30") (class "Default")
      (node (ref "DD1") (pin "30") (pinfunction "IO_30") (pintype "bidirectional"))
      (node (ref "X20") (pin "1") (pinfunction "1_1") (pintype "passive"))
      (node (ref "XP2") (pin "23") (pinfunction "23_23") (pintype "passive"))
    )
    (net (code "27") (name "/Pin33") (class "Default")
      (node (ref "DD1") (pin "33") (pinfunction "IO_33") (pintype "bidirectional"))
      (node (ref "X21") (pin "1") (pinfunction "1_1") (pintype "passive"))
      (node (ref "XP2") (pin "22") (pinfunction "22_22") (pintype "passive"))
    )
    (net (code "28") (name "/Pin34") (class "Default")
      (node (ref "DD1") (pin "34") (pinfunction "IO_34") (pintype "bidirectional"))
      (node (ref "X22") (pin "1") (pinfunction "1_1") (pintype "passive"))
      (node (ref "XP2") (pin "21") (pinfunction "21_21") (pintype "passive"))
    )
    (net (code "29") (name "/Pin35") (class "Default")
      (node (ref "DD1") (pin "35") (pinfunction "IO_35") (pintype "bidirectional"))
      (node (ref "X23") (pin "1") (pinfunction "1_1") (pintype "passive"))
      (node (ref "XP2") (pin "20") (pinfunction "20_20") (pintype "passive"))
    )
    (net (code "30") (name "/Pin36") (class "Default")
      (node (ref "DD1") (pin "36") (pinfunction "IO_36") (pintype "bidirectional"))
      (node (ref "X24") (pin "1") (pinfunction "1_1") (pintype "passive"))
      (node (ref "XP2") (pin "19") (pinfunction "19_19") (pintype "passive"))
    )
    (net (code "31") (name "/Pin37") (class "Default")
      (node (ref "DD1") (pin "37") (pinfunction "IO_37") (pintype "bidirectional"))
      (node (ref "X25") (pin "1") (pinfunction "1_1") (pintype "passive"))
      (node (ref "XP2") (pin "16") (pinfunction "16_16") (pintype "passive"))
    )
    (net (code "32") (name "/Pin38") (class "Default")
      (node (ref "DD1") (pin "38") (pinfunction "IO_38") (pintype "bidirectional"))
      (node (ref "X26") (pin "1") (pinfunction "1_1") (pintype "passive"))
      (node (ref "XP2") (pin "15") (pinfunction "15_15") (pintype "passive"))
    )
    (net (code "33") (name "/Pin39") (class "Default")
      (node (ref "DD1") (pin "39") (pinfunction "IO_39") (pintype "bidirectional"))
      (node (ref "X27") (pin "1") (pinfunction "1_1") (pintype "passive"))
      (node (ref "XP2") (pin "14") (pinfunction "14_14") (pintype "passive"))
    )
    (net (code "34") (name "/Pin40") (class "Default")
      (node (ref "DD1") (pin "40") (pinfunction "IO_40") (pintype "bidirectional"))
      (node (ref "X28") (pin "1") (pinfunction "1_1") (pintype "passive"))
      (node (ref "XP2") (pin "13") (pinfunction "13_13") (pintype "passive"))
    )
    (net (code "35") (name "/Pin41") (class "Default")
      (node (ref "DD1") (pin "41") (pinfunction "IO_41") (pintype "bidirectional"))
      (node (ref "X29") (pin "1") (pinfunction "1_1") (pintype "passive"))
      (node (ref "XP2") (pin "12") (pinfunction "12_12") (pintype "passive"))
    )
    (net (code "36") (name "/Pin42") (class "Default")
      (node (ref "DD1") (pin "42") (pinfunction "IO_42") (pintype "bidirectional"))
      (node (ref "X30") (pin "1") (pinfunction "1_1") (pintype "passive"))
      (node (ref "XP2") (pin "11") (pinfunction "11_11") (pintype "passive"))
    )
    (net (code "37") (name "/Pin43") (class "Default")
      (node (ref "DD1") (pin "43") (pinfunction "IO/DEV_OE_43") (pintype "bidirectional"))
      (node (ref "X31") (pin "1") (pinfunction "1_1") (pintype "passive"))
      (node (ref "XP2") (pin "8") (pinfunction "8_8") (pintype "passive"))
    )
    (net (code "38") (name "/Pin44") (class "Default")
      (node (ref "DD1") (pin "44") (pinfunction "IO/DEV_CLRn_44") (pintype "bidirectional"))
      (node (ref "X32") (pin "1") (pinfunction "1_1") (pintype "passive"))
      (node (ref "XP2") (pin "7") (pinfunction "7_7") (pintype "passive"))
    )
    (net (code "39") (name "/Pin47") (class "Default")
      (node (ref "DD1") (pin "47") (pinfunction "IO_47") (pintype "bidirectional"))
      (node (ref "X33") (pin "1") (pinfunction "1_1") (pintype "passive"))
      (node (ref "XP2") (pin "6") (pinfunction "6_6") (pintype "passive"))
    )
    (net (code "40") (name "/Pin48") (class "Default")
      (node (ref "DD1") (pin "48") (pinfunction "IO_48") (pintype "bidirectional"))
      (node (ref "X34") (pin "1") (pinfunction "1_1") (pintype "passive"))
      (node (ref "XP2") (pin "5") (pinfunction "5_5") (pintype "passive"))
    )
    (net (code "41") (name "/Pin49") (class "Default")
      (node (ref "DD1") (pin "49") (pinfunction "IO_49") (pintype "bidirectional"))
      (node (ref "X35") (pin "1") (pinfunction "1_1") (pintype "passive"))
      (node (ref "XP2") (pin "4") (pinfunction "4_4") (pintype "passive"))
    )
    (net (code "42") (name "/Pin50") (class "Default")
      (node (ref "DD1") (pin "50") (pinfunction "IO_50") (pintype "bidirectional"))
      (node (ref "R15") (pin "1") (pinfunction "1_1") (pintype "passive"))
      (node (ref "SB2") (pin "1") (pinfunction "COMMON_1") (pintype "passive"))
      (node (ref "X36") (pin "1") (pinfunction "1_1") (pintype "passive"))
      (node (ref "XP2") (pin "3") (pinfunction "3_3") (pintype "passive"))
    )
    (net (code "43") (name "/Pin51") (class "Default")
      (node (ref "DD1") (pin "51") (pinfunction "IO_51") (pintype "bidirectional"))
      (node (ref "X37") (pin "1") (pinfunction "1_1") (pintype "passive"))
      (node (ref "XP5") (pin "31") (pinfunction "31_31") (pintype "passive"))
    )
    (net (code "44") (name "/Pin52") (class "Default")
      (node (ref "DD1") (pin "52") (pinfunction "IO_52") (pintype "bidirectional"))
      (node (ref "X38") (pin "1") (pinfunction "1_1") (pintype "passive"))
      (node (ref "XP5") (pin "32") (pinfunction "32_32") (pintype "passive"))
    )
    (net (code "45") (name "/Pin53") (class "Default")
      (node (ref "DD1") (pin "53") (pinfunction "IO_53") (pintype "bidirectional"))
      (node (ref "X39") (pin "1") (pinfunction "1_1") (pintype "passive"))
      (node (ref "XP5") (pin "29") (pinfunction "29_29") (pintype "passive"))
    )
    (net (code "46") (name "/Pin54") (class "Default")
      (node (ref "DD1") (pin "54") (pinfunction "IO_54") (pintype "bidirectional"))
      (node (ref "X40") (pin "1") (pinfunction "1_1") (pintype "passive"))
      (node (ref "XP5") (pin "30") (pinfunction "30_30") (pintype "passive"))
    )
    (net (code "47") (name "/Pin55") (class "Default")
      (node (ref "DD1") (pin "55") (pinfunction "IO_55") (pintype "bidirectional"))
      (node (ref "X41") (pin "1") (pinfunction "1_1") (pintype "passive"))
      (node (ref "XP5") (pin "27") (pinfunction "27_27") (pintype "passive"))
    )
    (net (code "48") (name "/Pin56") (class "Default")
      (node (ref "DD1") (pin "56") (pinfunction "IO_56") (pintype "bidirectional"))
      (node (ref "X42") (pin "1") (pinfunction "1_1") (pintype "passive"))
      (node (ref "XP5") (pin "28") (pinfunction "28_28") (pintype "passive"))
    )
    (net (code "49") (name "/Pin57") (class "Default")
      (node (ref "DD1") (pin "57") (pinfunction "IO_57") (pintype "bidirectional"))
      (node (ref "X43") (pin "1") (pinfunction "1_1") (pintype "passive"))
      (node (ref "XP5") (pin "23") (pinfunction "23_23") (pintype "passive"))
    )
    (net (code "50") (name "/Pin58") (class "Default")
      (node (ref "DD1") (pin "58") (pinfunction "IO_58") (pintype "bidirectional"))
      (node (ref "X44") (pin "1") (pinfunction "1_1") (pintype "passive"))
      (node (ref "XP5") (pin "24") (pinfunction "24_24") (pintype "passive"))
    )
    (net (code "51") (name "/Pin61") (class "Default")
      (node (ref "DD1") (pin "61") (pinfunction "IO_61") (pintype "bidirectional"))
      (node (ref "X45") (pin "1") (pinfunction "1_1") (pintype "passive"))
      (node (ref "XP5") (pin "21") (pinfunction "21_21") (pintype "passive"))
    )
    (net (code "52") (name "/Pin62") (class "Default")
      (node (ref "DD1") (pin "62") (pinfunction "IO/GCLK2_62") (pintype "bidirectional"))
      (node (ref "X46") (pin "1") (pinfunction "1_1") (pintype "passive"))
      (node (ref "XP5") (pin "22") (pinfunction "22_22") (pintype "passive"))
    )
    (net (code "53") (name "/Pin64") (class "Default")
      (node (ref "DD1") (pin "64") (pinfunction "IO/GCLK3_64") (pintype "bidirectional"))
      (node (ref "X47") (pin "1") (pinfunction "1_1") (pintype "passive"))
      (node (ref "XP5") (pin "19") (pinfunction "19_19") (pintype "passive"))
    )
    (net (code "54") (name "/Pin66") (class "Default")
      (node (ref "DD1") (pin "66") (pinfunction "IO_66") (pintype "bidirectional"))
      (node (ref "X48") (pin "1") (pinfunction "1_1") (pintype "passive"))
      (node (ref "XP5") (pin "20") (pinfunction "20_20") (pintype "passive"))
    )
    (net (code "55") (name "/Pin67") (class "Default")
      (node (ref "DD1") (pin "67") (pinfunction "IO_67") (pintype "bidirectional"))
      (node (ref "X49") (pin "1") (pinfunction "1_1") (pintype "passive"))
      (node (ref "XP5") (pin "16") (pinfunction "16_16") (pintype "passive"))
    )
    (net (code "56") (name "/Pin68") (class "Default")
      (node (ref "DD1") (pin "68") (pinfunction "IO_68") (pintype "bidirectional"))
      (node (ref "X50") (pin "1") (pinfunction "1_1") (pintype "passive"))
      (node (ref "XP5") (pin "15") (pinfunction "15_15") (pintype "passive"))
    )
    (net (code "57") (name "/Pin69") (class "Default")
      (node (ref "DD1") (pin "69") (pinfunction "IO_69") (pintype "bidirectional"))
      (node (ref "X51") (pin "1") (pinfunction "1_1") (pintype "passive"))
      (node (ref "XP5") (pin "14") (pinfunction "14_14") (pintype "passive"))
    )
    (net (code "58") (name "/Pin70") (class "Default")
      (node (ref "DD1") (pin "70") (pinfunction "IO_70") (pintype "bidirectional"))
      (node (ref "X52") (pin "1") (pinfunction "1_1") (pintype "passive"))
      (node (ref "XP5") (pin "13") (pinfunction "13_13") (pintype "passive"))
    )
    (net (code "59") (name "/Pin71") (class "Default")
      (node (ref "DD1") (pin "71") (pinfunction "IO_71") (pintype "bidirectional"))
      (node (ref "X53") (pin "1") (pinfunction "1_1") (pintype "passive"))
      (node (ref "XP5") (pin "12") (pinfunction "12_12") (pintype "passive"))
    )
    (net (code "60") (name "/Pin72") (class "Default")
      (node (ref "DD1") (pin "72") (pinfunction "IO_72") (pintype "bidirectional"))
      (node (ref "DD2") (pin "20") (pinfunction "RX_20") (pintype "passive"))
      (node (ref "HL2") (pin "K") (pinfunction "K_K") (pintype "passive"))
      (node (ref "X54") (pin "1") (pinfunction "1_1") (pintype "passive"))
      (node (ref "XP5") (pin "11") (pinfunction "11_11") (pintype "passive"))
    )
    (net (code "61") (name "/Pin73") (class "Default")
      (node (ref "DD1") (pin "73") (pinfunction "IO_73") (pintype "bidirectional"))
      (node (ref "DD2") (pin "21") (pinfunction "TX_21") (pintype "passive"))
      (node (ref "HL1") (pin "K") (pinfunction "K_K") (pintype "passive"))
      (node (ref "X55") (pin "1") (pinfunction "1_1") (pintype "passive"))
      (node (ref "XP5") (pin "8") (pinfunction "8_8") (pintype "passive"))
    )
    (net (code "62") (name "/Pin74") (class "Default")
      (node (ref "DD1") (pin "74") (pinfunction "IO_74") (pintype "bidirectional"))
      (node (ref "DD2") (pin "23") (pinfunction "GPIO.2_CTS_23") (pintype "passive"))
      (node (ref "X56") (pin "1") (pinfunction "1_1") (pintype "passive"))
      (node (ref "XP5") (pin "7") (pinfunction "7_7") (pintype "passive"))
    )
    (net (code "63") (name "/Pin75") (class "Default")
      (node (ref "DD1") (pin "75") (pinfunction "IO_75") (pintype "bidirectional"))
      (node (ref "DD2") (pin "24") (pinfunction "GPIO.1_RTS_24") (pintype "passive"))
      (node (ref "X57") (pin "1") (pinfunction "1_1") (pintype "passive"))
      (node (ref "XP5") (pin "6") (pinfunction "6_6") (pintype "passive"))
    )
    (net (code "64") (name "/Pin76") (class "Default")
      (node (ref "DD1") (pin "76") (pinfunction "IO_76") (pintype "bidirectional"))
      (node (ref "R6") (pin "2") (pinfunction "2_2") (pintype "passive"))
      (node (ref "X58") (pin "1") (pinfunction "1_1") (pintype "passive"))
      (node (ref "XP6") (pin "31") (pinfunction "31_31") (pintype "passive"))
    )
    (net (code "65") (name "/Pin77") (class "Default")
      (node (ref "DD1") (pin "77") (pinfunction "IO_77") (pintype "bidirectional"))
      (node (ref "R16") (pin "2") (pinfunction "2_2") (pintype "passive"))
      (node (ref "X59") (pin "1") (pinfunction "1_1") (pintype "passive"))
      (node (ref "XP6") (pin "29") (pinfunction "29_29") (pintype "passive"))
    )
    (net (code "66") (name "/Pin78") (class "Default")
      (node (ref "DD1") (pin "78") (pinfunction "IO_78") (pintype "bidirectional"))
      (node (ref "R17") (pin "2") (pinfunction "2_2") (pintype "passive"))
      (node (ref "X60") (pin "1") (pinfunction "1_1") (pintype "passive"))
      (node (ref "XP6") (pin "27") (pinfunction "27_27") (pintype "passive"))
    )
    (net (code "67") (name "/Pin81") (class "Default")
      (node (ref "DD1") (pin "81") (pinfunction "IO_81") (pintype "bidirectional"))
      (node (ref "R18") (pin "2") (pinfunction "2_2") (pintype "passive"))
      (node (ref "X61") (pin "1") (pinfunction "1_1") (pintype "passive"))
      (node (ref "XP6") (pin "28") (pinfunction "28_28") (pintype "passive"))
    )
    (net (code "68") (name "/Pin82") (class "Default")
      (node (ref "DD1") (pin "82") (pinfunction "IO_82") (pintype "bidirectional"))
      (node (ref "R19") (pin "2") (pinfunction "2_2") (pintype "passive"))
      (node (ref "X62") (pin "1") (pinfunction "1_1") (pintype "passive"))
      (node (ref "XP6") (pin "23") (pinfunction "23_23") (pintype "passive"))
    )
    (net (code "69") (name "/Pin83") (class "Default")
      (node (ref "DD1") (pin "83") (pinfunction "IO_83") (pintype "bidirectional"))
      (node (ref "R20") (pin "2") (pinfunction "2_2") (pintype "passive"))
      (node (ref "X63") (pin "1") (pinfunction "1_1") (pintype "passive"))
      (node (ref "XP6") (pin "24") (pinfunction "24_24") (pintype "passive"))
    )
    (net (code "70") (name "/Pin84") (class "Default")
      (node (ref "DD1") (pin "84") (pinfunction "IO_84") (pintype "bidirectional"))
      (node (ref "R21") (pin "2") (pinfunction "2_2") (pintype "passive"))
      (node (ref "X64") (pin "1") (pinfunction "1_1") (pintype "passive"))
      (node (ref "XP6") (pin "21") (pinfunction "21_21") (pintype "passive"))
    )
    (net (code "71") (name "/Pin85") (class "Default")
      (node (ref "DD1") (pin "85") (pinfunction "IO_85") (pintype "bidirectional"))
      (node (ref "R22") (pin "2") (pinfunction "2_2") (pintype "passive"))
      (node (ref "X65") (pin "1") (pinfunction "1_1") (pintype "passive"))
      (node (ref "XP6") (pin "22") (pinfunction "22_22") (pintype "passive"))
    )
    (net (code "72") (name "/Pin86") (class "Default")
      (node (ref "DD1") (pin "86") (pinfunction "IO_86") (pintype "bidirectional"))
      (node (ref "X66") (pin "1") (pinfunction "1_1") (pintype "passive"))
      (node (ref "XP6") (pin "19") (pinfunction "19_19") (pintype "passive"))
    )
    (net (code "73") (name "/Pin87") (class "Default")
      (node (ref "DD1") (pin "87") (pinfunction "IO_87") (pintype "bidirectional"))
      (node (ref "X67") (pin "1") (pinfunction "1_1") (pintype "passive"))
      (node (ref "XP6") (pin "20") (pinfunction "20_20") (pintype "passive"))
    )
    (net (code "74") (name "/Pin88") (class "Default")
      (node (ref "DD1") (pin "88") (pinfunction "IO_88") (pintype "bidirectional"))
      (node (ref "X68") (pin "1") (pinfunction "1_1") (pintype "passive"))
      (node (ref "XP6") (pin "16") (pinfunction "16_16") (pintype "passive"))
    )
    (net (code "75") (name "/Pin89") (class "Default")
      (node (ref "DD1") (pin "89") (pinfunction "IO_89") (pintype "bidirectional"))
      (node (ref "X69") (pin "1") (pinfunction "1_1") (pintype "passive"))
      (node (ref "XP6") (pin "15") (pinfunction "15_15") (pintype "passive"))
    )
    (net (code "76") (name "/Pin90") (class "Default")
      (node (ref "DD1") (pin "90") (pinfunction "IO_90") (pintype "bidirectional"))
      (node (ref "X70") (pin "1") (pinfunction "1_1") (pintype "passive"))
      (node (ref "XP6") (pin "14") (pinfunction "14_14") (pintype "passive"))
    )
    (net (code "77") (name "/Pin91") (class "Default")
      (node (ref "DD1") (pin "91") (pinfunction "IO_91") (pintype "bidirectional"))
      (node (ref "X71") (pin "1") (pinfunction "1_1") (pintype "passive"))
      (node (ref "XP6") (pin "13") (pinfunction "13_13") (pintype "passive"))
    )
    (net (code "78") (name "/Pin92") (class "Default")
      (node (ref "DD1") (pin "92") (pinfunction "IO_92") (pintype "bidirectional"))
      (node (ref "X72") (pin "1") (pinfunction "1_1") (pintype "passive"))
      (node (ref "XP6") (pin "12") (pinfunction "12_12") (pintype "passive"))
    )
    (net (code "79") (name "/Pin95") (class "Default")
      (node (ref "DD1") (pin "95") (pinfunction "IO_95") (pintype "bidirectional"))
      (node (ref "X73") (pin "1") (pinfunction "1_1") (pintype "passive"))
      (node (ref "XP6") (pin "11") (pinfunction "11_11") (pintype "passive"))
    )
    (net (code "80") (name "/Pin96") (class "Default")
      (node (ref "DD1") (pin "96") (pinfunction "IO_96") (pintype "bidirectional"))
      (node (ref "X74") (pin "1") (pinfunction "1_1") (pintype "passive"))
      (node (ref "XP6") (pin "8") (pinfunction "8_8") (pintype "passive"))
    )
    (net (code "81") (name "/Pin97") (class "Default")
      (node (ref "DD1") (pin "97") (pinfunction "IO_97") (pintype "bidirectional"))
      (node (ref "X75") (pin "1") (pinfunction "1_1") (pintype "passive"))
      (node (ref "XP6") (pin "7") (pinfunction "7_7") (pintype "passive"))
    )
    (net (code "82") (name "/Pin98") (class "Default")
      (node (ref "DD1") (pin "98") (pinfunction "IO_98") (pintype "bidirectional"))
      (node (ref "X76") (pin "1") (pinfunction "1_1") (pintype "passive"))
      (node (ref "XP6") (pin "6") (pinfunction "6_6") (pintype "passive"))
    )
    (net (code "83") (name "/Pin99") (class "Default")
      (node (ref "DD1") (pin "99") (pinfunction "IO_99") (pintype "bidirectional"))
      (node (ref "X77") (pin "1") (pinfunction "1_1") (pintype "passive"))
      (node (ref "XP6") (pin "5") (pinfunction "5_5") (pintype "passive"))
    )
    (net (code "84") (name "/Pin100") (class "Default")
      (node (ref "DD1") (pin "100") (pinfunction "IO_100") (pintype "bidirectional"))
      (node (ref "X78") (pin "1") (pinfunction "1_1") (pintype "passive"))
      (node (ref "XP6") (pin "3") (pinfunction "3_3") (pintype "passive"))
    )
    (net (code "85") (name "/TCK") (class "Default")
      (node (ref "DD1") (pin "24") (pinfunction "TCK_24") (pintype "input"))
      (node (ref "R4") (pin "1") (pinfunction "1_1") (pintype "passive"))
      (node (ref "XP4") (pin "1") (pinfunction "1_1") (pintype "passive"))
      (node (ref "XP7") (pin "3") (pinfunction "3_3") (pintype "passive"))
    )
    (net (code "86") (name "/TDI") (class "Default")
      (node (ref "DD1") (pin "23") (pinfunction "TDI_23") (pintype "input"))
      (node (ref "R3") (pin "1") (pinfunction "1_1") (pintype "passive"))
      (node (ref "XP4") (pin "9") (pinfunction "9_9") (pintype "passive"))
      (node (ref "XP7") (pin "2") (pinfunction "2_2") (pintype "passive"))
    )
    (net (code "87") (name "/TDO") (class "Default")
      (node (ref "DD1") (pin "25") (pinfunction "TDO_25") (pintype "output"))
      (node (ref "R1") (pin "1") (pinfunction "1_1") (pintype "passive"))
      (node (ref "XP4") (pin "3") (pinfunction "3_3") (pintype "passive"))
      (node (ref "XP7") (pin "4") (pinfunction "4_4") (pintype "passive"))
    )
    (net (code "88") (name "/TMS") (class "Default")
      (node (ref "DD1") (pin "22") (pinfunction "TMS_22") (pintype "input"))
      (node (ref "R2") (pin "1") (pinfunction "1_1") (pintype "passive"))
      (node (ref "XP4") (pin "5") (pinfunction "5_5") (pintype "passive"))
      (node (ref "XP7") (pin "1") (pinfunction "1_1") (pintype "passive"))
    )
    (net (code "89") (name "CLK_5") (class "Default")
      (node (ref "DD3") (pin "8") (pinfunction "4Y_8") (pintype "passive"))
      (node (ref "X80") (pin "1") (pinfunction "1_1") (pintype "passive"))
    )
    (net (code "90") (name "GND") (class "Default")
      (node (ref "C1") (pin "1") (pinfunction "1_1") (pintype "passive"))
      (node (ref "C10") (pin "1") (pinfunction "1_1") (pintype "passive"))
      (node (ref "C11") (pin "1") (pinfunction "1_1") (pintype "passive"))
      (node (ref "C12") (pin "1") (pinfunction "1_1") (pintype "passive"))
      (node (ref "C13") (pin "1") (pinfunction "1_1") (pintype "passive"))
      (node (ref "C14") (pin "1") (pinfunction "1_1") (pintype "passive"))
      (node (ref "C15") (pin "1") (pinfunction "1_1") (pintype "passive"))
      (node (ref "C16") (pin "1") (pinfunction "1_1") (pintype "passive"))
      (node (ref "C17") (pin "1") (pinfunction "1_1") (pintype "passive"))
      (node (ref "C18") (pin "1") (pinfunction "1_1") (pintype "passive"))
      (node (ref "C19") (pin "1") (pinfunction "1_1") (pintype "passive"))
      (node (ref "C2") (pin "1") (pinfunction "1_1") (pintype "passive"))
      (node (ref "C20") (pin "1") (pinfunction "1_1") (pintype "passive"))
      (node (ref "C21") (pin "1") (pinfunction "1_1") (pintype "passive"))
      (node (ref "C22") (pin "1") (pinfunction "1_1") (pintype "passive"))
      (node (ref "C23") (pin "1") (pinfunction "1_1") (pintype "passive"))
      (node (ref "C24") (pin "1") (pinfunction "1_1") (pintype "passive"))
      (node (ref "C25") (pin "1") (pinfunction "1_1") (pintype "passive"))
      (node (ref "C26") (pin "1") (pinfunction "1_1") (pintype "passive"))
      (node (ref "C27") (pin "2") (pinfunction "2_2") (pintype "passive"))
      (node (ref "C28") (pin "1") (pinfunction "1_1") (pintype "passive"))
      (node (ref "C29") (pin "1") (pinfunction "1_1") (pintype "passive"))
      (node (ref "C3") (pin "1") (pinfunction "1_1") (pintype "passive"))
      (node (ref "C30") (pin "1") (pinfunction "1_1") (pintype "passive"))
      (node (ref "C4") (pin "1") (pinfunction "1_1") (pintype "passive"))
      (node (ref "C5") (pin "1") (pinfunction "1_1") (pintype "passive"))
      (node (ref "C6") (pin "1") (pinfunction "1_1") (pintype "passive"))
      (node (ref "C7") (pin "1") (pinfunction "1_1") (pintype "passive"))
      (node (ref "C8") (pin "1") (pinfunction "1_1") (pintype "passive"))
      (node (ref "C9") (pin "1") (pinfunction "1_1") (pintype "passive"))
      (node (ref "DA1") (pin "1") (pinfunction "Gnd_1") (pintype "passive"))
      (node (ref "DD1") (pin "10") (pinfunction "GNDIO_10") (pintype "power_in"))
      (node (ref "DD1") (pin "11") (pinfunction "GNDINT_11") (pintype "power_in"))
      (node (ref "DD1") (pin "32") (pinfunction "GNDIO_32") (pintype "power_in"))
      (node (ref "DD1") (pin "46") (pinfunction "GNDIO_46") (pintype "power_in"))
      (node (ref "DD1") (pin "60") (pinfunction "GNDIO_60") (pintype "power_in"))
      (node (ref "DD1") (pin "65") (pinfunction "GNDINT_65") (pintype "power_in"))
      (node (ref "DD1") (pin "79") (pinfunction "GNDIO_79") (pintype "power_in"))
      (node (ref "DD1") (pin "93") (pinfunction "GNDIO_93") (pintype "power_in"))
      (node (ref "DD2") (pin "2") (pinfunction "GND_2") (pintype "passive"))
      (node (ref "DD2") (pin "25") (pinfunction "EPad_25") (pintype "passive"))
      (node (ref "DD3") (pin "7") (pinfunction "GND_7") (pintype "power_in"))
      (node (ref "HL10") (pin "K") (pinfunction "K_K") (pintype "passive"))
      (node (ref "HL3") (pin "K") (pinfunction "K_K") (pintype "passive"))
      (node (ref "HL4") (pin "K") (pinfunction "K_K") (pintype "passive"))
      (node (ref "HL5") (pin "K") (pinfunction "K_K") (pintype "passive"))
      (node (ref "HL6") (pin "K") (pinfunction "K_K") (pintype "passive"))
      (node (ref "HL7") (pin "K") (pinfunction "K_K") (pintype "passive"))
      (node (ref "HL8") (pin "K") (pinfunction "K_K") (pintype "passive"))
      (node (ref "HL9") (pin "K") (pinfunction "K_K") (pintype "passive"))
      (node (ref "Q1") (pin "2") (pinfunction "Gnd_2") (pintype "passive"))
      (node (ref "R14") (pin "2") (pinfunction "2_2") (pintype "passive"))
      (node (ref "R15") (pin "2") (pinfunction "2_2") (pintype "passive"))
      (node (ref "R4") (pin "2") (pinfunction "2_2") (pintype "passive"))
      (node (ref "XP1") (pin "10") (pinfunction "10_10") (pintype "passive"))
      (node (ref "XP1") (pin "18") (pinfunction "18_18") (pintype "passive"))
      (node (ref "XP1") (pin "2") (pinfunction "2_2") (pintype "passive"))
      (node (ref "XP1") (pin "26") (pinfunction "26_26") (pintype "passive"))
      (node (ref "XP1") (pin "34") (pinfunction "34_34") (pintype "passive"))
      (node (ref "XP2") (pin "10") (pinfunction "10_10") (pintype "passive"))
      (node (ref "XP2") (pin "18") (pinfunction "18_18") (pintype "passive"))
      (node (ref "XP2") (pin "2") (pinfunction "2_2") (pintype "passive"))
      (node (ref "XP2") (pin "26") (pinfunction "26_26") (pintype "passive"))
      (node (ref "XP2") (pin "34") (pinfunction "34_34") (pintype "passive"))
      (node (ref "XP4") (pin "10") (pinfunction "10_10") (pintype "passive"))
      (node (ref "XP4") (pin "2") (pinfunction "2_2") (pintype "passive"))
      (node (ref "XP5") (pin "10") (pinfunction "10_10") (pintype "passive"))
      (node (ref "XP5") (pin "18") (pinfunction "18_18") (pintype "passive"))
      (node (ref "XP5") (pin "2") (pinfunction "2_2") (pintype "passive"))
      (node (ref "XP5") (pin "26") (pinfunction "26_26") (pintype "passive"))
      (node (ref "XP5") (pin "34") (pinfunction "34_34") (pintype "passive"))
      (node (ref "XP6") (pin "10") (pinfunction "10_10") (pintype "passive"))
      (node (ref "XP6") (pin "18") (pinfunction "18_18") (pintype "passive"))
      (node (ref "XP6") (pin "2") (pinfunction "2_2") (pintype "passive"))
      (node (ref "XP6") (pin "26") (pinfunction "26_26") (pintype "passive"))
      (node (ref "XP6") (pin "34") (pinfunction "34_34") (pintype "passive"))
      (node (ref "XP7") (pin "5") (pinfunction "5_5") (pintype "passive"))
      (node (ref "XS1") (pin "5") (pinfunction "5_5") (pintype "passive"))
    )
    (net (code "91") (name "Net-(C28-Pad2)") (class "Default")
      (node (ref "C28") (pin "2") (pinfunction "2_2") (pintype "passive"))
      (node (ref "G1") (pin "2") (pinfunction "2_2") (pintype "passive"))
      (node (ref "R11") (pin "1") (pinfunction "1_1") (pintype "passive"))
    )
    (net (code "92") (name "Net-(C30-Pad2)") (class "Default")
      (node (ref "C30") (pin "2") (pinfunction "2_2") (pintype "passive"))
      (node (ref "G2") (pin "2") (pinfunction "2_2") (pintype "passive"))
      (node (ref "R13") (pin "1") (pinfunction "1_1") (pintype "passive"))
    )
    (net (code "93") (name "Net-(DD2-D+)") (class "Default")
      (node (ref "DD2") (pin "3") (pinfunction "D+_3") (pintype "passive"))
      (node (ref "XS1") (pin "3") (pinfunction "3_3") (pintype "passive"))
    )
    (net (code "94") (name "Net-(DD2-D-)") (class "Default")
      (node (ref "DD2") (pin "4") (pinfunction "D-_4") (pintype "passive"))
      (node (ref "XS1") (pin "2") (pinfunction "2_2") (pintype "passive"))
    )
    (net (code "95") (name "Net-(DD2-VPP)") (class "Default")
      (node (ref "C21") (pin "2") (pinfunction "2_2") (pintype "passive"))
      (node (ref "DD2") (pin "16") (pinfunction "VPP_16") (pintype "passive"))
    )
    (net (code "96") (name "Net-(DD2-~{RST})") (class "Default")
      (node (ref "DD2") (pin "9") (pinfunction "~{RST}_9") (pintype "passive"))
      (node (ref "R7") (pin "2") (pinfunction "2_2") (pintype "passive"))
    )
    (net (code "97") (name "Net-(DD3A-1A)") (class "Default")
      (node (ref "C26") (pin "2") (pinfunction "2_2") (pintype "passive"))
      (node (ref "DD3") (pin "1") (pinfunction "1A_1") (pintype "passive"))
      (node (ref "G1") (pin "1") (pinfunction "1_1") (pintype "passive"))
      (node (ref "R10") (pin "1") (pinfunction "1_1") (pintype "passive"))
    )
    (net (code "98") (name "Net-(DD3A-1Y)") (class "Default")
      (node (ref "DD3") (pin "2") (pinfunction "1Y_2") (pintype "passive"))
      (node (ref "DD3") (pin "3") (pinfunction "2A_3") (pintype "passive"))
      (node (ref "R10") (pin "2") (pinfunction "2_2") (pintype "passive"))
      (node (ref "R11") (pin "2") (pinfunction "2_2") (pintype "passive"))
    )
    (net (code "99") (name "Net-(DD3C-3A)") (class "Default")
      (node (ref "C29") (pin "2") (pinfunction "2_2") (pintype "passive"))
      (node (ref "DD3") (pin "5") (pinfunction "3A_5") (pintype "passive"))
      (node (ref "G2") (pin "1") (pinfunction "1_1") (pintype "passive"))
      (node (ref "R12") (pin "1") (pinfunction "1_1") (pintype "passive"))
    )
    (net (code "100") (name "Net-(DD3C-3Y)") (class "Default")
      (node (ref "DD3") (pin "6") (pinfunction "3Y_6") (pintype "passive"))
      (node (ref "DD3") (pin "9") (pinfunction "4A_9") (pintype "passive"))
      (node (ref "R12") (pin "2") (pinfunction "2_2") (pintype "passive"))
      (node (ref "R13") (pin "2") (pinfunction "2_2") (pintype "passive"))
    )
    (net (code "101") (name "Net-(HL1-PadA)") (class "Default")
      (node (ref "HL1") (pin "A") (pinfunction "A_A") (pintype "passive"))
      (node (ref "R8") (pin "1") (pinfunction "1_1") (pintype "passive"))
    )
    (net (code "102") (name "Net-(HL2-PadA)") (class "Default")
      (node (ref "HL2") (pin "A") (pinfunction "A_A") (pintype "passive"))
      (node (ref "R9") (pin "1") (pinfunction "1_1") (pintype "passive"))
    )
    (net (code "103") (name "Net-(HL3-PadA)") (class "Default")
      (node (ref "HL3") (pin "A") (pinfunction "A_A") (pintype "passive"))
      (node (ref "R6") (pin "1") (pinfunction "1_1") (pintype "passive"))
    )
    (net (code "104") (name "Net-(HL4-PadA)") (class "Default")
      (node (ref "HL4") (pin "A") (pinfunction "A_A") (pintype "passive"))
      (node (ref "R16") (pin "1") (pinfunction "1_1") (pintype "passive"))
    )
    (net (code "105") (name "Net-(HL5-PadA)") (class "Default")
      (node (ref "HL5") (pin "A") (pinfunction "A_A") (pintype "passive"))
      (node (ref "R17") (pin "1") (pinfunction "1_1") (pintype "passive"))
    )
    (net (code "106") (name "Net-(HL6-PadA)") (class "Default")
      (node (ref "HL6") (pin "A") (pinfunction "A_A") (pintype "passive"))
      (node (ref "R18") (pin "1") (pinfunction "1_1") (pintype "passive"))
    )
    (net (code "107") (name "Net-(HL7-PadA)") (class "Default")
      (node (ref "HL7") (pin "A") (pinfunction "A_A") (pintype "passive"))
      (node (ref "R19") (pin "1") (pinfunction "1_1") (pintype "passive"))
    )
    (net (code "108") (name "Net-(HL8-PadA)") (class "Default")
      (node (ref "HL8") (pin "A") (pinfunction "A_A") (pintype "passive"))
      (node (ref "R20") (pin "1") (pinfunction "1_1") (pintype "passive"))
    )
    (net (code "109") (name "Net-(HL9-PadA)") (class "Default")
      (node (ref "HL9") (pin "A") (pinfunction "A_A") (pintype "passive"))
      (node (ref "R21") (pin "1") (pinfunction "1_1") (pintype "passive"))
    )
    (net (code "110") (name "Net-(HL10-PadA)") (class "Default")
      (node (ref "HL10") (pin "A") (pinfunction "A_A") (pintype "passive"))
      (node (ref "R22") (pin "1") (pinfunction "1_1") (pintype "passive"))
    )
    (net (code "111") (name "Net-(L1-Pad1)") (class "Default")
      (node (ref "L1") (pin "1") (pinfunction "1_1") (pintype "passive"))
      (node (ref "XS1") (pin "1") (pinfunction "1_1") (pintype "passive"))
    )
    (net (code "112") (name "Net-(Q1-Out)") (class "Default")
      (node (ref "Q1") (pin "3") (pinfunction "Out_3") (pintype "passive"))
      (node (ref "R5") (pin "1") (pinfunction "1_1") (pintype "passive"))
    )
    (net (code "113") (name "unconnected-(DD2-GPIO.0_{slash}_CLK-Pad1)") (class "Default")
      (node (ref "DD2") (pin "1") (pinfunction "GPIO.0_/_CLK_1") (pintype "passive+no_connect"))
    )
    (net (code "114") (name "unconnected-(DD2-GPIO.3_RS485-Pad22)") (class "Default")
      (node (ref "DD2") (pin "22") (pinfunction "GPIO.3_RS485_22") (pintype "passive+no_connect"))
    )
    (net (code "115") (name "unconnected-(DD2-GPIO.4_TXT-Pad19)") (class "Default")
      (node (ref "DD2") (pin "19") (pinfunction "GPIO.4_TXT_19") (pintype "passive+no_connect"))
    )
    (net (code "116") (name "unconnected-(DD2-GPIO.5_RXT-Pad18)") (class "Default")
      (node (ref "DD2") (pin "18") (pinfunction "GPIO.5_RXT_18") (pintype "passive+no_connect"))
    )
    (net (code "117") (name "unconnected-(DD2-GPIO.6-Pad15)") (class "Default")
      (node (ref "DD2") (pin "15") (pinfunction "GPIO.6_15") (pintype "passive+no_connect"))
    )
    (net (code "118") (name "unconnected-(DD2-GPIO.7-Pad14)") (class "Default")
      (node (ref "DD2") (pin "14") (pinfunction "GPIO.7_14") (pintype "passive+no_connect"))
    )
    (net (code "119") (name "unconnected-(DD2-GPIO.8-Pad13)") (class "Default")
      (node (ref "DD2") (pin "13") (pinfunction "GPIO.8_13") (pintype "passive+no_connect"))
    )
    (net (code "120") (name "unconnected-(DD2-GPIO.9-Pad12)") (class "Default")
      (node (ref "DD2") (pin "12") (pinfunction "GPIO.9_12") (pintype "passive+no_connect"))
    )
    (net (code "121") (name "unconnected-(DD2-NC-Pad10)") (class "Default")
      (node (ref "DD2") (pin "10") (pinfunction "NC_10") (pintype "passive+no_connect"))
    )
    (net (code "122") (name "unconnected-(DD2-SUSPEND-Pad11)") (class "Default")
      (node (ref "DD2") (pin "11") (pinfunction "SUSPEND_11") (pintype "passive+no_connect"))
    )
    (net (code "123") (name "unconnected-(DD2-~{SUSPEND}-Pad17)") (class "Default")
      (node (ref "DD2") (pin "17") (pinfunction "~{SUSPEND}_17") (pintype "passive+no_connect"))
    )
    (net (code "124") (name "unconnected-(XP1-Pad3)") (class "Default")
      (node (ref "XP1") (pin "3") (pinfunction "3_3") (pintype "passive"))
    )
    (net (code "125") (name "unconnected-(XP1-Pad4)") (class "Default")
      (node (ref "XP1") (pin "4") (pinfunction "4_4") (pintype "passive"))
    )
    (net (code "126") (name "unconnected-(XP1-Pad5)") (class "Default")
      (node (ref "XP1") (pin "5") (pinfunction "5_5") (pintype "passive"))
    )
    (net (code "127") (name "unconnected-(XP1-Pad6)") (class "Default")
      (node (ref "XP1") (pin "6") (pinfunction "6_6") (pintype "passive"))
    )
    (net (code "128") (name "unconnected-(XP1-Pad7)") (class "Default")
      (node (ref "XP1") (pin "7") (pinfunction "7_7") (pintype "passive"))
    )
    (net (code "129") (name "unconnected-(XP1-Pad8)") (class "Default")
      (node (ref "XP1") (pin "8") (pinfunction "8_8") (pintype "passive"))
    )
    (net (code "130") (name "unconnected-(XP1-Pad11)") (class "Default")
      (node (ref "XP1") (pin "11") (pinfunction "11_11") (pintype "passive"))
    )
    (net (code "131") (name "unconnected-(XP1-Pad12)") (class "Default")
      (node (ref "XP1") (pin "12") (pinfunction "12_12") (pintype "passive"))
    )
    (net (code "132") (name "unconnected-(XP2-Pad30)") (class "Default")
      (node (ref "XP2") (pin "30") (pinfunction "30_30") (pintype "passive"))
    )
    (net (code "133") (name "unconnected-(XP2-Pad31)") (class "Default")
      (node (ref "XP2") (pin "31") (pinfunction "31_31") (pintype "passive"))
    )
    (net (code "134") (name "unconnected-(XP2-Pad32)") (class "Default")
      (node (ref "XP2") (pin "32") (pinfunction "32_32") (pintype "passive"))
    )
    (net (code "135") (name "unconnected-(XP4-Pad6)") (class "Default")
      (node (ref "XP4") (pin "6") (pinfunction "6_6") (pintype "passive"))
    )
    (net (code "136") (name "unconnected-(XP4-Pad7)") (class "Default")
      (node (ref "XP4") (pin "7") (pinfunction "7_7") (pintype "passive"))
    )
    (net (code "137") (name "unconnected-(XP4-Pad8)") (class "Default")
      (node (ref "XP4") (pin "8") (pinfunction "8_8") (pintype "passive"))
    )
    (net (code "138") (name "unconnected-(XP5-Pad3)") (class "Default")
      (node (ref "XP5") (pin "3") (pinfunction "3_3") (pintype "passive"))
    )
    (net (code "139") (name "unconnected-(XP5-Pad4)") (class "Default")
      (node (ref "XP5") (pin "4") (pinfunction "4_4") (pintype "passive"))
    )
    (net (code "140") (name "unconnected-(XP5-Pad5)") (class "Default")
      (node (ref "XP5") (pin "5") (pinfunction "5_5") (pintype "passive"))
    )
    (net (code "141") (name "unconnected-(XP6-Pad4)") (class "Default")
      (node (ref "XP6") (pin "4") (pinfunction "4_4") (pintype "passive"))
    )
    (net (code "142") (name "unconnected-(XP6-Pad30)") (class "Default")
      (node (ref "XP6") (pin "30") (pinfunction "30_30") (pintype "passive"))
    )
    (net (code "143") (name "unconnected-(XP6-Pad32)") (class "Default")
      (node (ref "XP6") (pin "32") (pinfunction "32_32") (pintype "passive"))
    )
    (net (code "144") (name "unconnected-(XS1-Pad4)") (class "Default")
      (node (ref "XS1") (pin "4") (pinfunction "4_4") (pintype "passive"))
    )
  )
)
